# LA200-GZ.net
KiCad netlist of a schematic drawn in Altium Designer
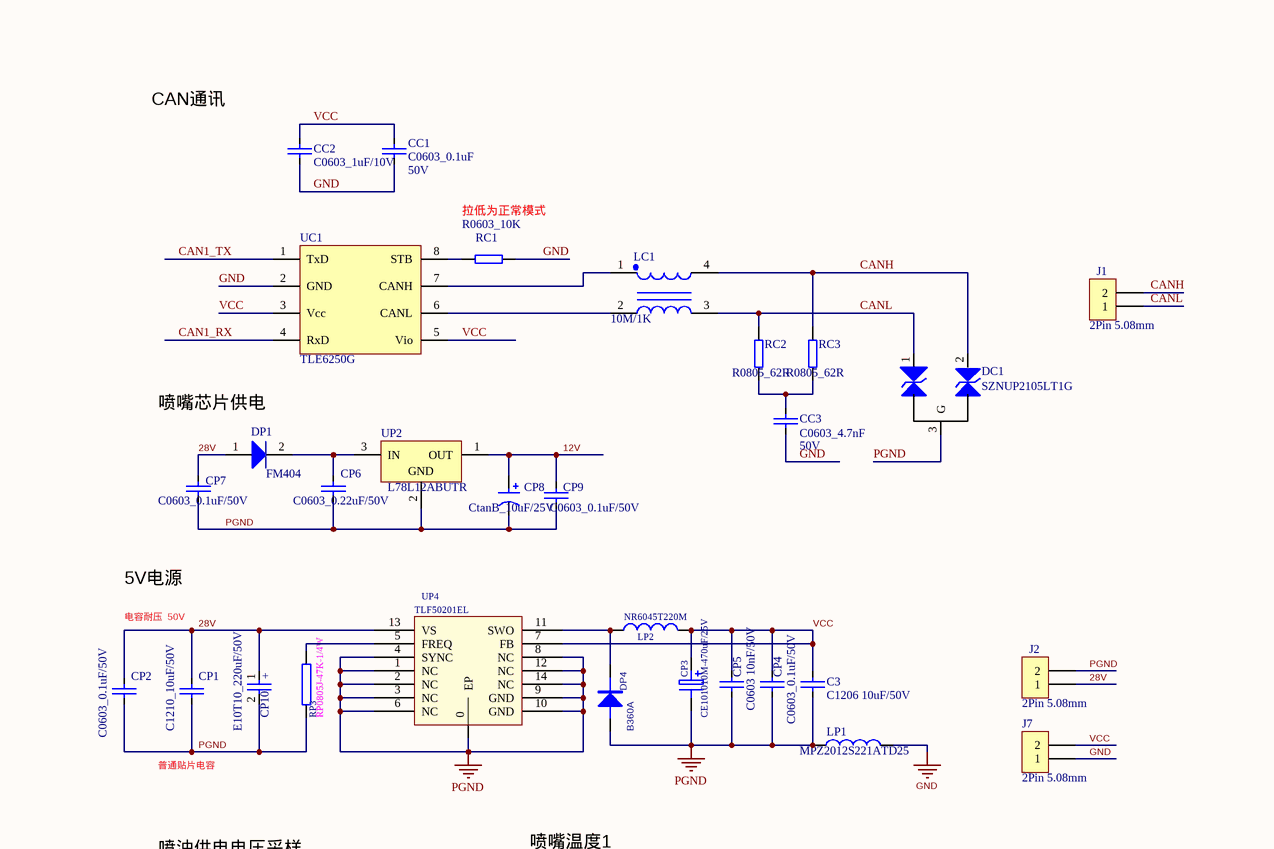
[diagram p0: LA200-GZ.SchDoc, top left]
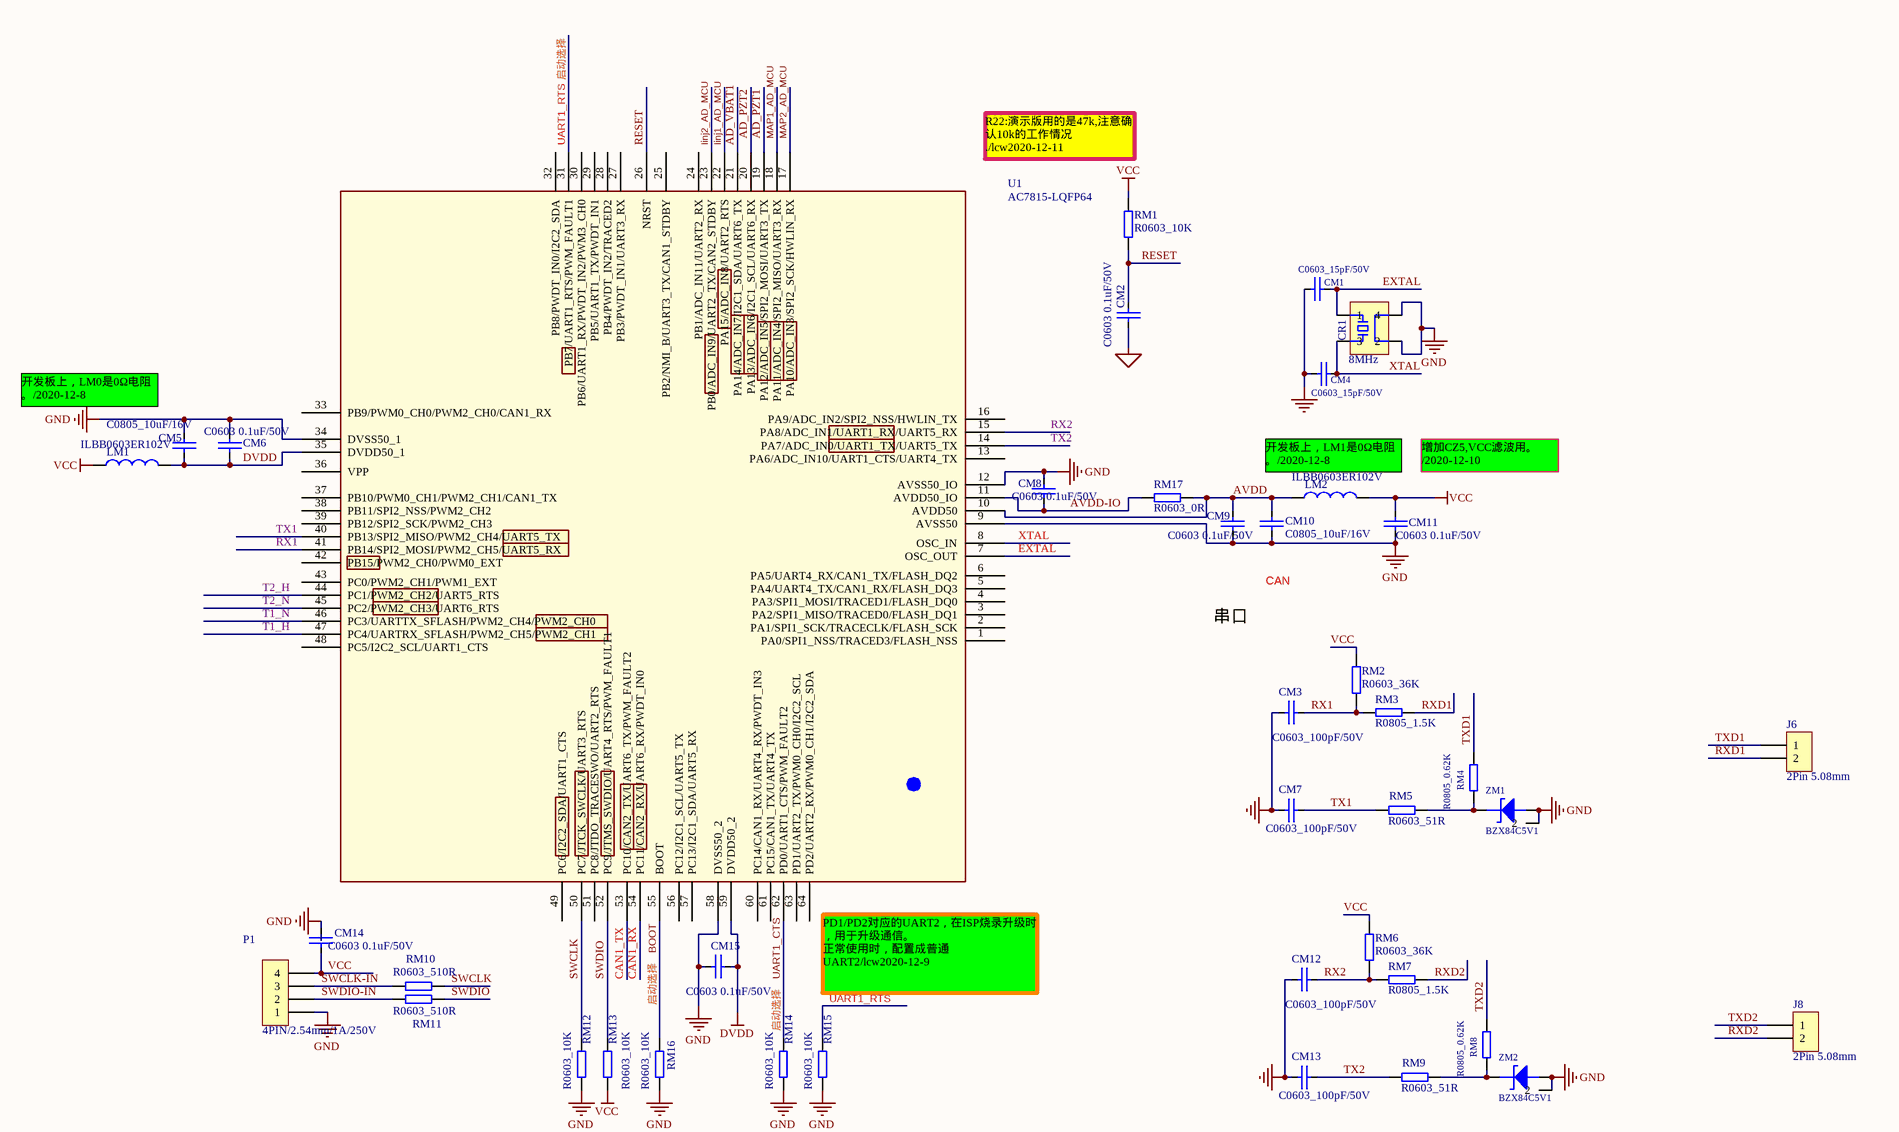
[diagram p1: LA200-GZ.SchDoc, top right]
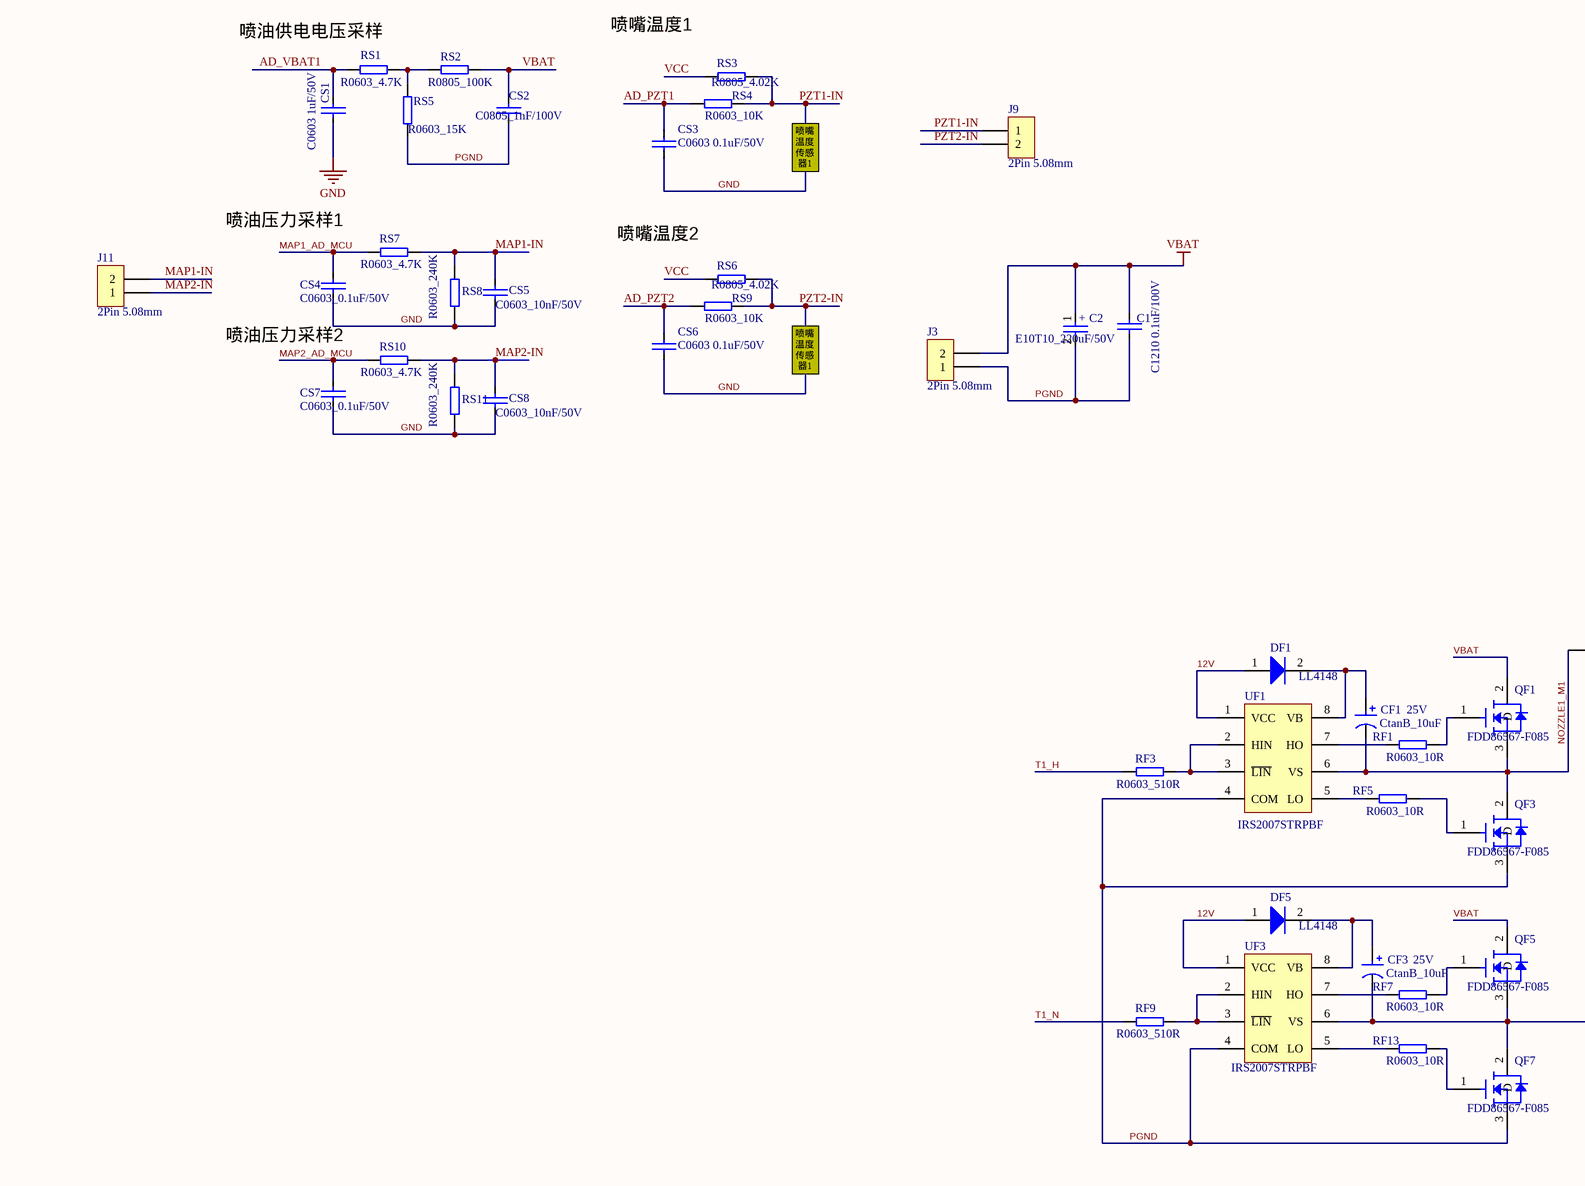
[diagram p2: LA200-GZ.SchDoc, bottom left]
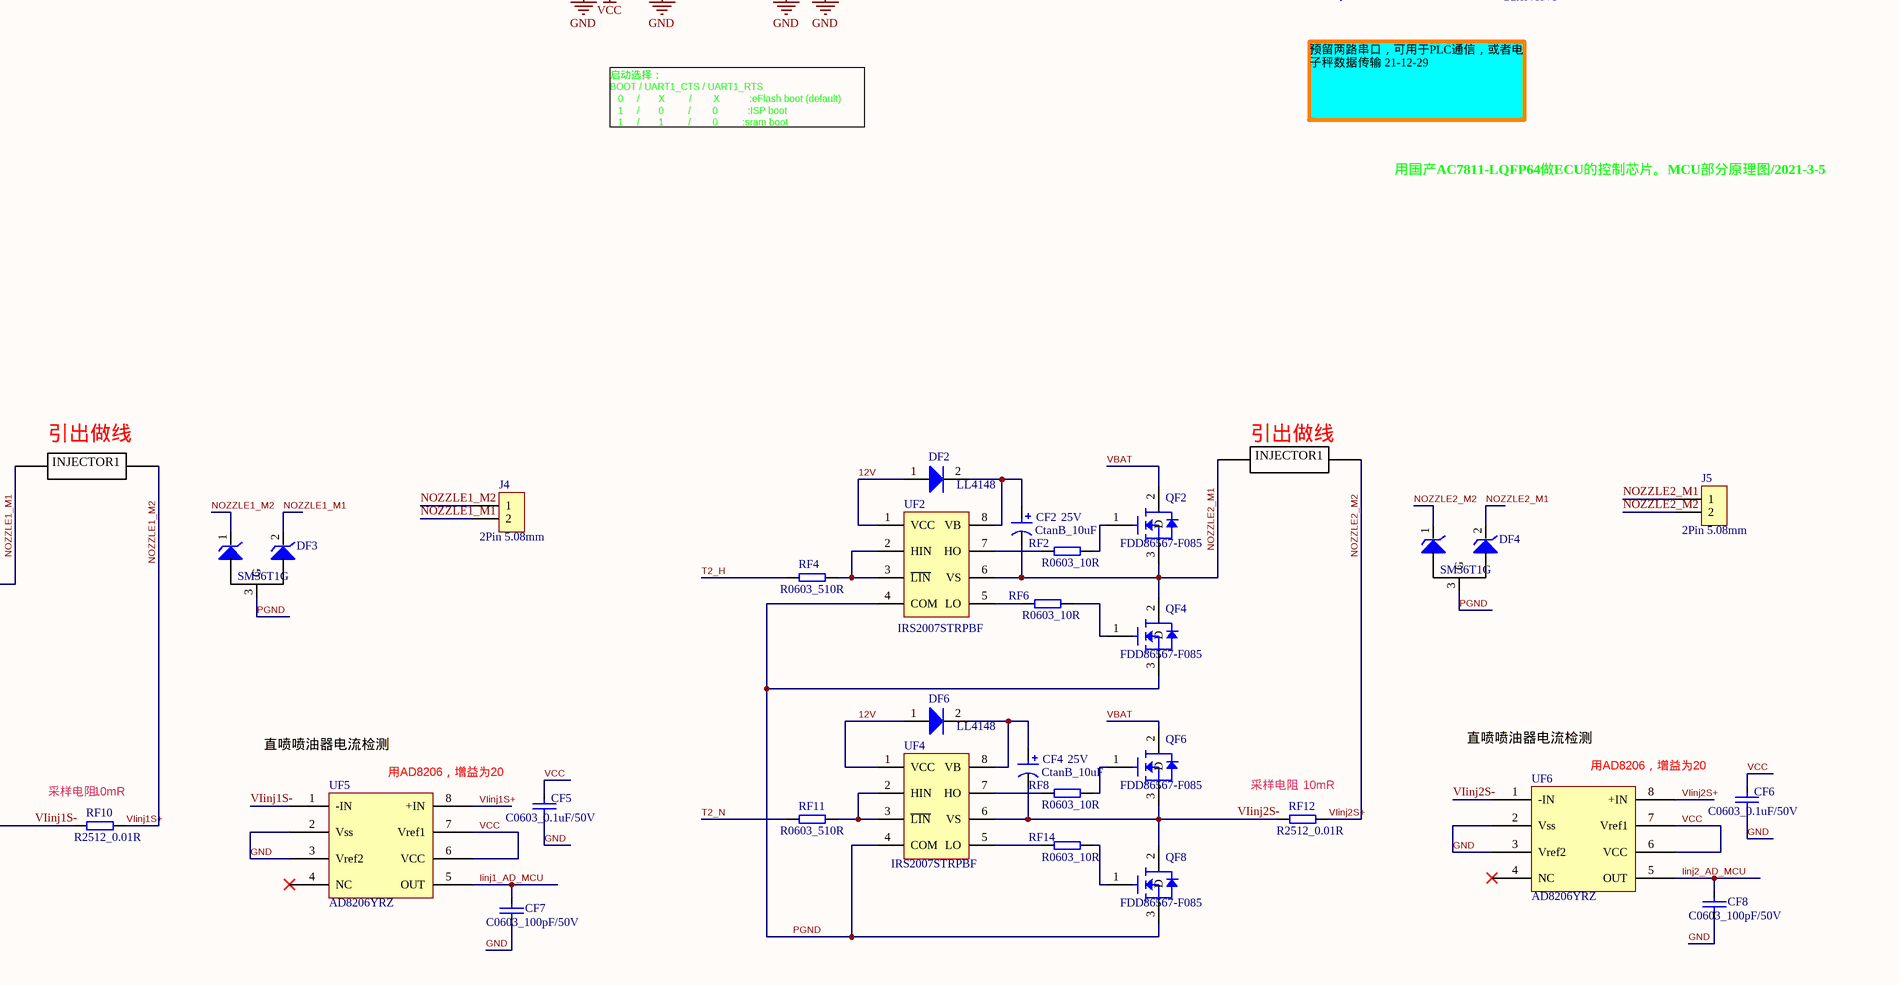
[diagram p3: LA200-GZ.SchDoc, bottom right]

(export (version "E")
  (design (tool "Eeschema 10.0.6"))
  (components
    (comp (ref "C1")
      (value "C1210 0.1uF/100V")
      (footprint "C1210")
      (description "C1210 0.1uF/50V 10%")
      (fields (field (name "VOLTAGE") "100V") (field (name "PART NUMBER") "3170014005"))
      (libsource (lib "BMSer") (part "CAP"))
    )
    (comp (ref "C2")
      (value "E10T10_220uF/50V")
      (footprint "E10T10")
      (description "E10T10 220uF/50V 20%")
      (fields (field (name "PART NUMBER") "3172690040") (field (name "MANUFACTURER") "LELON"))
      (libsource (lib "BMSer") (part "CAP_E"))
    )
    (comp (ref "C3")
      (value "C1206 10uF/50V")
      (footprint "C1206")
      (description "C1206 10uF/50V  10%")
      (fields (field (name "VOLTAGE") "50V") (field (name "PART NUMBER") "3172530019"))
      (libsource (lib "BMSer") (part "CAP"))
    )
    (comp (ref "CC1")
      (value "C0603_0.1uF")
      (footprint "C0603")
      (description "C0603 0.1uF/50V 10%")
      (fields
        (field (name "VOLTAGE") "50V")
        (field (name "PART NUMBER") "3170011015")
        (field (name "MANUFACTURER") "YAGEO")
      )
      (libsource (lib "BMSer") (part "CAP"))
    )
    (comp (ref "CC2")
      (value "C0603_1uF/10V")
      (footprint "C0603")
      (description "C0603 0.1uF/50V 10%")
      (fields (field (name "VOLTAGE") "10V") (field (name "PART NUMBER") "3170011015"))
      (libsource (lib "BMSer") (part "CAP"))
    )
    (comp (ref "CC3")
      (value "C0603_4.7nF")
      (footprint "C0603")
      (description "C0603 4.7nF/50V 5% X7R")
      (fields
        (field (name "VOLTAGE") "50V")
        (field (name "PART NUMBER") "3170011009")
        (field (name "MANUFACTURER") "YAGEO")
      )
      (libsource (lib "BMSer") (part "CAP"))
    )
    (comp (ref "CF1")
      (value "CtanB_10uF")
      (footprint "CTANB")
      (description "CtanB(1210) 10uF/25V 10%")
      (fields
        (field (name "PART NUMBER") "3172690034")
        (field (name "MANUFACTURER") "AVX")
        (field (name "VOLTAGE") "25V")
      )
      (libsource (lib "BMSer") (part "CAP_T"))
    )
    (comp (ref "CF2")
      (value "CtanB_10uF")
      (footprint "CTANB")
      (description "CtanB(1210) 10uF/25V 10%")
      (fields
        (field (name "PART NUMBER") "3172690034")
        (field (name "MANUFACTURER") "AVX")
        (field (name "VOLTAGE") "25V")
      )
      (libsource (lib "BMSer") (part "CAP_T"))
    )
    (comp (ref "CF3")
      (value "CtanB_10uF")
      (footprint "CTANB")
      (description "CtanB(1210) 10uF/25V 10%")
      (fields
        (field (name "PART NUMBER") "3172690034")
        (field (name "MANUFACTURER") "AVX")
        (field (name "VOLTAGE") "25V")
      )
      (libsource (lib "BMSer") (part "CAP_T"))
    )
    (comp (ref "CF4")
      (value "CtanB_10uF")
      (footprint "CTANB")
      (description "CtanB(1210) 10uF/25V 10%")
      (fields
        (field (name "PART NUMBER") "3172690034")
        (field (name "MANUFACTURER") "AVX")
        (field (name "VOLTAGE") "25V")
      )
      (libsource (lib "BMSer") (part "CAP_T"))
    )
    (comp (ref "CF5")
      (value "C0603_0.1uF/50V")
      (footprint "C0603")
      (description "C0603 0.1uF/50V 10%")
      (fields (field (name "VOLTAGE") "50V") (field (name "PART NUMBER") "3170011015"))
      (libsource (lib "BMSer") (part "CAP"))
    )
    (comp (ref "CF6")
      (value "C0603_0.1uF/50V")
      (footprint "C0603")
      (description "C0603 0.1uF/50V 10%")
      (fields (field (name "VOLTAGE") "50V") (field (name "PART NUMBER") "3170011015"))
      (libsource (lib "BMSer") (part "CAP"))
    )
    (comp (ref "CF7")
      (value "C0603_100pF/50V")
      (footprint "C0603")
      (description "C0603 100pF/50V 5%")
      (fields (field (name "VOLTAGE") "50V") (field (name "PART NUMBER") "3170011003"))
      (libsource (lib "BMSer") (part "CAP"))
    )
    (comp (ref "CF8")
      (value "C0603_100pF/50V")
      (footprint "C0603")
      (description "C0603 100pF/50V 5%")
      (fields (field (name "VOLTAGE") "50V") (field (name "PART NUMBER") "3170011003"))
      (libsource (lib "BMSer") (part "CAP"))
    )
    (comp (ref "CM1")
      (value "C0603_15pF/50V")
      (footprint "C0603")
      (description "C0603 15pF/50V 10%")
      (fields (field (name "VOLTAGE") "50V") (field (name "PART NUMBER") "3172510040"))
      (libsource (lib "BMSer") (part "CAP"))
    )
    (comp (ref "CM2")
      (value "C0603 0.1uF/50V")
      (footprint "C0603")
      (description "C0603 0.1uF/50V 10%")
      (fields (field (name "VOLTAGE") "50V") (field (name "PART NUMBER") "3170011015"))
      (libsource (lib "BMSer") (part "CAP"))
    )
    (comp (ref "CM3")
      (value "C0603_100pF/50V")
      (footprint "C0603")
      (description "C0603 100pF/50V 5%")
      (fields (field (name "VOLTAGE") "50V") (field (name "PART NUMBER") "3170011003"))
      (libsource (lib "BMSer") (part "CAP"))
    )
    (comp (ref "CM4")
      (value "C0603_15pF/50V")
      (footprint "C0603")
      (description "C0603 15pF/50V 10%")
      (fields (field (name "VOLTAGE") "50V") (field (name "PART NUMBER") "3172510040"))
      (libsource (lib "BMSer") (part "CAP"))
    )
    (comp (ref "CM5")
      (value "C0805_10uF/16V")
      (footprint "C0805")
      (description "C0805 10uF/16V 10%")
      (fields (field (name "VOLTAGE") "16V") (field (name "PART NUMBER") "3170012008"))
      (libsource (lib "BMSer") (part "CAP"))
    )
    (comp (ref "CM6")
      (value "C0603 0.1uF/50V")
      (footprint "C0603")
      (description "C0603 0.1uF/50V 10%")
      (fields (field (name "VOLTAGE") "50V") (field (name "PART NUMBER") "3170011015"))
      (libsource (lib "BMSer") (part "CAP"))
    )
    (comp (ref "CM7")
      (value "C0603_100pF/50V")
      (footprint "C0603")
      (description "C0603 100pF/50V 5%")
      (fields (field (name "VOLTAGE") "50V") (field (name "PART NUMBER") "3170011003"))
      (libsource (lib "BMSer") (part "CAP"))
    )
    (comp (ref "CM8")
      (value "C0603 0.1uF/50V")
      (footprint "C0603")
      (description "C0603 0.1uF/50V 10%")
      (fields (field (name "VOLTAGE") "50V") (field (name "PART NUMBER") "3170011015"))
      (libsource (lib "BMSer") (part "CAP"))
    )
    (comp (ref "CM9")
      (value "C0603 0.1uF/50V")
      (footprint "C0603")
      (description "C0603 0.1uF/50V 10%")
      (fields (field (name "VOLTAGE") "50V") (field (name "PART NUMBER") "3170011015"))
      (libsource (lib "BMSer") (part "CAP"))
    )
    (comp (ref "CM10")
      (value "C0805_10uF/16V")
      (footprint "C0805")
      (description "C0805 10uF/16V 10%")
      (fields (field (name "VOLTAGE") "16V") (field (name "PART NUMBER") "3170012008"))
      (libsource (lib "BMSer") (part "CAP"))
    )
    (comp (ref "CM11")
      (value "C0603 0.1uF/50V")
      (footprint "C0603")
      (description "C0603 0.1uF/50V 10%")
      (fields (field (name "VOLTAGE") "50V") (field (name "PART NUMBER") "3170011015"))
      (libsource (lib "BMSer") (part "CAP"))
    )
    (comp (ref "CM12")
      (value "C0603_100pF/50V")
      (footprint "C0603")
      (description "C0603 100pF/50V 5%")
      (fields (field (name "VOLTAGE") "50V") (field (name "PART NUMBER") "3170011003"))
      (libsource (lib "BMSer") (part "CAP"))
    )
    (comp (ref "CM13")
      (value "C0603_100pF/50V")
      (footprint "C0603")
      (description "C0603 100pF/50V 5%")
      (fields (field (name "VOLTAGE") "50V") (field (name "PART NUMBER") "3170011003"))
      (libsource (lib "BMSer") (part "CAP"))
    )
    (comp (ref "CM14")
      (value "C0603 0.1uF/50V")
      (footprint "C0603")
      (description "C0603 0.1uF/50V 10%")
      (fields (field (name "VOLTAGE") "50V") (field (name "PART NUMBER") "3170011015"))
      (libsource (lib "BMSer") (part "CAP"))
    )
    (comp (ref "CM15")
      (value "C0603 0.1uF/50V")
      (footprint "C0603")
      (description "C0603 0.1uF/50V 10%")
      (fields (field (name "VOLTAGE") "50V") (field (name "PART NUMBER") "3170011015"))
      (libsource (lib "BMSer") (part "CAP"))
    )
    (comp (ref "CP1")
      (value "C1210_10uF/50V")
      (footprint "C1210")
      (description "C1210 10uF/50V 10%")
      (fields (field (name "VOLTAGE") "50V") (field (name "PART NUMBER") "3170014011"))
      (libsource (lib "BMSer") (part "CAP"))
    )
    (comp (ref "CP2")
      (value "C0603_0.1uF/50V")
      (footprint "C0603")
      (description "C0603 0.1uF/50V 10%")
      (fields (field (name "VOLTAGE") "50V") (field (name "PART NUMBER") "3170011015"))
      (libsource (lib "BMSer") (part "CAP"))
    )
    (comp (ref "CP3")
      (value "CE101010M-470uF/25V")
      (footprint "E10T10")
      (libsource (lib "*") (part "ELECTRO1"))
    )
    (comp (ref "CP4")
      (value "C0603_0.1uF/50V")
      (footprint "C0603")
      (description "C0603 0.1uF/50V 10%")
      (fields (field (name "VOLTAGE") "50V") (field (name "PART NUMBER") "3170011015"))
      (libsource (lib "BMSer") (part "CAP"))
    )
    (comp (ref "CP5")
      (value "C0603 10nF/50V")
      (footprint "C0603")
      (description "C0603 10nF/50V  10%")
      (fields (field (name "VOLTAGE") "50V") (field (name "PART NUMBER") "3170011011"))
      (libsource (lib "BMSer") (part "CAP"))
    )
    (comp (ref "CP6")
      (value "C0603_0.22uF/50V")
      (footprint "C0603")
      (description "C0603 0.22uF/50V 10%")
      (fields (field (name "VOLTAGE") "50V") (field (name "PART NUMBER") "3172510028"))
      (libsource (lib "BMSer") (part "CAP"))
    )
    (comp (ref "CP7")
      (value "C0603_0.1uF/50V")
      (footprint "C0603")
      (description "C0603 0.1uF/50V 10%")
      (fields (field (name "VOLTAGE") "50V") (field (name "PART NUMBER") "3170011015"))
      (libsource (lib "BMSer") (part "CAP"))
    )
    (comp (ref "CP8")
      (value "CtanB_10uF/25V")
      (footprint "CTANB")
      (description "CtanB(1210) 10uF/25V 10%")
      (fields (field (name "PART NUMBER") "3172690034") (field (name "MANUFACTURER") "AVX"))
      (libsource (lib "BMSer") (part "CAP_T"))
    )
    (comp (ref "CP9")
      (value "C0603_0.1uF/50V")
      (footprint "C0603")
      (description "C0603 0.1uF/50V 10%")
      (fields (field (name "VOLTAGE") "50V") (field (name "PART NUMBER") "3170011015"))
      (libsource (lib "BMSer") (part "CAP"))
    )
    (comp (ref "CP10")
      (value "E10T10_220uF/50V")
      (footprint "E10T10")
      (description "E10T10 220uF/50V 20%")
      (fields (field (name "PART NUMBER") "3172690040") (field (name "MANUFACTURER") "LELON"))
      (libsource (lib "BMSer") (part "CAP_E"))
    )
    (comp (ref "CR1")
      (value "8MHz")
      (footprint "5.0*3.2*0.9mm AB")
      (description "5.0*3.2*0.9mm AB 8MHz")
      (fields (field (name "PART NUMBER") "53120010024") (field (name "MANUFACTURER") "TXC"))
      (libsource (lib "BMSer") (part "XTAL_1"))
    )
    (comp (ref "CS1")
      (value "C0603 1uF/50V")
      (footprint "C0603")
      (description "C0603 1uF/50V 10%")
      (fields (field (name "VOLTAGE") "50V") (field (name "PART NUMBER") "3172510036"))
      (libsource (lib "BMSer") (part "CAP"))
    )
    (comp (ref "CS2")
      (value "C0805_1nF/100V")
      (footprint "C0805")
      (description "C0805 1nF/100V 10%")
      (fields (field (name "VOLTAGE") "100V") (field (name "PART NUMBER") "3172520028"))
      (libsource (lib "BMSer") (part "CAP"))
    )
    (comp (ref "CS3")
      (value "C0603 0.1uF/50V")
      (footprint "C0603")
      (description "C0603 0.1uF/50V 10%")
      (fields (field (name "VOLTAGE") "50V") (field (name "PART NUMBER") "3170011015"))
      (libsource (lib "BMSer") (part "CAP"))
    )
    (comp (ref "CS4")
      (value "C0603_0.1uF/50V")
      (footprint "C0603")
      (description "C0603 0.1uF/50V 10%")
      (fields (field (name "VOLTAGE") "50V") (field (name "PART NUMBER") "3170011015"))
      (libsource (lib "BMSer") (part "CAP"))
    )
    (comp (ref "CS5")
      (value "C0603_10nF/50V")
      (footprint "C0603")
      (description "C0603 10nF/50V  10%")
      (fields (field (name "VOLTAGE") "50V") (field (name "PART NUMBER") "3170011011"))
      (libsource (lib "BMSer") (part "CAP"))
    )
    (comp (ref "CS6")
      (value "C0603 0.1uF/50V")
      (footprint "C0603")
      (description "C0603 0.1uF/50V 10%")
      (fields (field (name "VOLTAGE") "50V") (field (name "PART NUMBER") "3170011015"))
      (libsource (lib "BMSer") (part "CAP"))
    )
    (comp (ref "CS7")
      (value "C0603_0.1uF/50V")
      (footprint "C0603")
      (description "C0603 0.1uF/50V 10%")
      (fields (field (name "VOLTAGE") "50V") (field (name "PART NUMBER") "3170011015"))
      (libsource (lib "BMSer") (part "CAP"))
    )
    (comp (ref "CS8")
      (value "C0603_10nF/50V")
      (footprint "C0603")
      (description "C0603 10nF/50V  10%")
      (fields (field (name "VOLTAGE") "50V") (field (name "PART NUMBER") "3170011011"))
      (libsource (lib "BMSer") (part "CAP"))
    )
    (comp (ref "DC1")
      (value "SZNUP2105LT1G")
      (footprint "SOT-23")
      (description "SOT-23 SZNUP2105LT1G")
      (fields (field (name "PART NUMBER") "3110050073") (field (name "MANUFACTURER") "ON"))
      (libsource (lib "BMSer") (part "SZNUP2105LT1G"))
    )
    (comp (ref "DF1")
      (value "LL4148")
      (footprint "SOD-80")
      (description "SOD-80  LL4148 2A/75V")
      (fields (field (name "PART NUMBER") "3110010015") (field (name "MANUFACTURER") "VISHA"))
      (libsource (lib "BMSer") (part "DIODE"))
    )
    (comp (ref "DF2")
      (value "LL4148")
      (footprint "SOD-80")
      (description "SOD-80  LL4148 2A/75V")
      (fields (field (name "PART NUMBER") "3110010015") (field (name "MANUFACTURER") "VISHA"))
      (libsource (lib "BMSer") (part "DIODE"))
    )
    (comp (ref "DF3")
      (value "SM36T1G")
      (footprint "SOT-23")
      (description "SOT-23 SM36T1G")
      (fields (field (name "PART NUMBER") "3110050074") (field (name "MANUFACTURER") "ON"))
      (libsource (lib "BMSer") (part "SM36T1G"))
    )
    (comp (ref "DF4")
      (value "SM36T1G")
      (footprint "SOT-23")
      (description "SOT-23 SM36T1G")
      (fields (field (name "PART NUMBER") "3110050074") (field (name "MANUFACTURER") "ON"))
      (libsource (lib "BMSer") (part "SM36T1G"))
    )
    (comp (ref "DF5")
      (value "LL4148")
      (footprint "SOD-80")
      (description "SOD-80  LL4148 2A/75V")
      (fields (field (name "PART NUMBER") "3110010015") (field (name "MANUFACTURER") "VISHA"))
      (libsource (lib "BMSer") (part "DIODE"))
    )
    (comp (ref "DF6")
      (value "LL4148")
      (footprint "SOD-80")
      (description "SOD-80  LL4148 2A/75V")
      (fields (field (name "PART NUMBER") "3110010015") (field (name "MANUFACTURER") "VISHA"))
      (libsource (lib "BMSer") (part "DIODE"))
    )
    (comp (ref "DP1")
      (value "FM404")
      (footprint "D0-214AC")
      (description "D0-214AC FM404")
      (fields (field (name "PART NUMBER") "13110010013") (field (name "MANUFACTURER") "LRC"))
      (libsource (lib "BMSer") (part "DIODE"))
    )
    (comp (ref "DP4")
      (value "B360A")
      (footprint "SMA-DIODE")
      (description "60V,1A,肖特基二极管")
      (libsource (lib "*") (part "DIODE"))
    )
    (comp (ref "J1")
      (value "2Pin 5.08mm")
      (footprint "CONN-TH_2P-P5.08_DB128L-5.08-2P")
      (description "691311500002 2Pin 5.08mm 公头")
      (fields (field (name "PART NUMBER") "31900010141") (field (name "MANUFACTURER") "WE"))
      (libsource (lib "") (part "CON2_1"))
    )
    (comp (ref "J2")
      (value "2Pin 5.08mm")
      (footprint "CONN-TH_2P-P5.08_DB128L-5.08-2P")
      (description "691311500002 2Pin 5.08mm 公头")
      (fields (field (name "PART NUMBER") "31900010141") (field (name "MANUFACTURER") "WE"))
      (libsource (lib "") (part "CON2_1"))
    )
    (comp (ref "J3")
      (value "2Pin 5.08mm")
      (footprint "CONN-TH_2P-P5.08_DB128L-5.08-2P")
      (description "691311500002 2Pin 5.08mm 公头")
      (fields (field (name "PART NUMBER") "31900010141") (field (name "MANUFACTURER") "WE"))
      (libsource (lib "") (part "CON2_1"))
    )
    (comp (ref "J4")
      (value "2Pin 5.08mm")
      (footprint "CONN-TH_2P-P5.08_DB128L-5.08-2P")
      (description "691311500002 2Pin 5.08mm 公头")
      (fields (field (name "PART NUMBER") "31900010141") (field (name "MANUFACTURER") "WE"))
      (libsource (lib "BMSer") (part "CON2"))
    )
    (comp (ref "J5")
      (value "2Pin 5.08mm")
      (footprint "CONN-TH_2P-P5.08_DB128L-5.08-2P")
      (description "691311500002 2Pin 5.08mm 公头")
      (fields (field (name "PART NUMBER") "31900010141") (field (name "MANUFACTURER") "WE"))
      (libsource (lib "BMSer") (part "CON2"))
    )
    (comp (ref "J6")
      (value "2Pin 5.08mm")
      (footprint "CONN-TH_2P-P5.08_DB128L-5.08-2P")
      (description "691311500002 2Pin 5.08mm 公头")
      (fields (field (name "PART NUMBER") "31900010141") (field (name "MANUFACTURER") "WE"))
      (libsource (lib "BMSer") (part "CON2"))
    )
    (comp (ref "J7")
      (value "2Pin 5.08mm")
      (footprint "CONN-TH_2P-P5.08_DB128L-5.08-2P")
      (description "691311500002 2Pin 5.08mm 公头")
      (fields (field (name "PART NUMBER") "31900010141") (field (name "MANUFACTURER") "WE"))
      (libsource (lib "") (part "CON2_1"))
    )
    (comp (ref "J8")
      (value "2Pin 5.08mm")
      (footprint "CONN-TH_2P-P5.08_DB128L-5.08-2P")
      (description "691311500002 2Pin 5.08mm 公头")
      (fields (field (name "PART NUMBER") "31900010141") (field (name "MANUFACTURER") "WE"))
      (libsource (lib "BMSer") (part "CON2"))
    )
    (comp (ref "J9")
      (value "2Pin 5.08mm")
      (footprint "CONN-TH_2P-P5.08_DB128L-5.08-2P")
      (description "691311500002 2Pin 5.08mm 公头")
      (fields (field (name "PART NUMBER") "31900010141") (field (name "MANUFACTURER") "WE"))
      (libsource (lib "BMSer") (part "CON2"))
    )
    (comp (ref "J11")
      (value "2Pin 5.08mm")
      (footprint "CONN-TH_2P-P5.08_DB128L-5.08-2P")
      (description "691311500002 2Pin 5.08mm 公头")
      (fields (field (name "PART NUMBER") "31900010141") (field (name "MANUFACTURER") "WE"))
      (libsource (lib "") (part "CON2_1"))
    )
    (comp (ref "LC1")
      (value "10M/1K")
      (footprint "ACT45B")
      (description "ACT45B-510-2P-TL  10M/1K/0.2A")
      (fields (field (name "PART NUMBER") "3180020022") (field (name "MANUFACTURER") "TDK"))
      (libsource (lib "BMSer") (part "INDUCTOR3"))
    )
    (comp (ref "LM1")
      (value "ILBB0603ER102V")
      (footprint "L0603")
      (description "L0603 ILBB0603ER102V")
      (fields (field (name "PART NUMBER") "3180020002") (field (name "MANUFACTURER") "Vishay"))
      (libsource (lib "BMSer") (part "INDUCTOR1"))
    )
    (comp (ref "LM2")
      (value "ILBB0603ER102V")
      (footprint "L0603")
      (description "L0603 ILBB0603ER102V")
      (fields (field (name "PART NUMBER") "3180020002") (field (name "MANUFACTURER") "Vishay"))
      (libsource (lib "BMSer") (part "INDUCTOR1"))
    )
    (comp (ref "LP1")
      (value "MPZ2012S221ATD25")
      (footprint "L 0805")
      (description "L0805 MPZ2012S221ATD25")
      (fields (field (name "PART NUMBER") "53180020011") (field (name "MANUFACTURER") "TDK"))
      (libsource (lib "BMSer") (part "INDUCTOR1"))
    )
    (comp (ref "LP2")
      (value "NR6045T220M")
      (footprint "L_6045")
      (description "22uH/1.9A")
      (libsource (lib "Miscellaneous Devices") (part "Inductor"))
    )
    (comp (ref "P1")
      (value "4PIN/2.54mm/1A/250V")
      (footprint "IDC-SIP-4P-2.54")
      (description "直针插座 CWF25404D180 4PIN/2.54mm/1A/250V")
      (fields (field (name "PART NUMBER") "3190010008") (field (name "MANUFACTURER") "CSCONN 德科泰"))
      (libsource (lib "BMSer") (part "CON4"))
    )
    (comp (ref "QF1")
      (value "FDD86567-F085")
      (footprint "TO-252-3")
      (description "TO-252-3 FDD86567-F085 60V/100A")
      (fields (field (name "PART NUMBER") "53110022012") (field (name "MANUFACTURER") "ON"))
      (libsource (lib "BMSer") (part "NMOSGDS"))
    )
    (comp (ref "QF2")
      (value "FDD86567-F085")
      (footprint "TO-252-3")
      (description "TO-252-3 FDD86567-F085 60V/100A")
      (fields (field (name "PART NUMBER") "53110022012") (field (name "MANUFACTURER") "ON"))
      (libsource (lib "BMSer") (part "NMOSGDS"))
    )
    (comp (ref "QF3")
      (value "FDD86567-F085")
      (footprint "TO-252-3")
      (description "TO-252-3 FDD86567-F085 60V/100A")
      (fields (field (name "PART NUMBER") "53110022012") (field (name "MANUFACTURER") "ON"))
      (libsource (lib "BMSer") (part "NMOSGDS"))
    )
    (comp (ref "QF4")
      (value "FDD86567-F085")
      (footprint "TO-252-3")
      (description "TO-252-3 FDD86567-F085 60V/100A")
      (fields (field (name "PART NUMBER") "53110022012") (field (name "MANUFACTURER") "ON"))
      (libsource (lib "BMSer") (part "NMOSGDS"))
    )
    (comp (ref "QF5")
      (value "FDD86567-F085")
      (footprint "TO-252-3")
      (description "TO-252-3 FDD86567-F085 60V/100A")
      (fields (field (name "PART NUMBER") "53110022012") (field (name "MANUFACTURER") "ON"))
      (libsource (lib "BMSer") (part "NMOSGDS"))
    )
    (comp (ref "QF6")
      (value "FDD86567-F085")
      (footprint "TO-252-3")
      (description "TO-252-3 FDD86567-F085 60V/100A")
      (fields (field (name "PART NUMBER") "53110022012") (field (name "MANUFACTURER") "ON"))
      (libsource (lib "BMSer") (part "NMOSGDS"))
    )
    (comp (ref "QF7")
      (value "FDD86567-F085")
      (footprint "TO-252-3")
      (description "TO-252-3 FDD86567-F085 60V/100A")
      (fields (field (name "PART NUMBER") "53110022012") (field (name "MANUFACTURER") "ON"))
      (libsource (lib "BMSer") (part "NMOSGDS"))
    )
    (comp (ref "QF8")
      (value "FDD86567-F085")
      (footprint "TO-252-3")
      (description "TO-252-3 FDD86567-F085 60V/100A")
      (fields (field (name "PART NUMBER") "53110022012") (field (name "MANUFACTURER") "ON"))
      (libsource (lib "BMSer") (part "NMOSGDS"))
    )
    (comp (ref "RC1")
      (value "R0603_10K")
      (footprint "R0603")
      (description "R0603 1/10w 10K 1%")
      (fields (field (name "PART NUMBER") "3160030053") (field (name "MANUFACTURER") "YAGEO"))
      (libsource (lib "BMSer") (part "RS"))
    )
    (comp (ref "RC2")
      (value "R0805_62R")
      (footprint "R0805")
      (description "R0805 1/8w10R 1%")
      (fields (field (name "PART NUMBER") "3160050016") (field (name "MANUFACTURER") "YAGEO"))
      (libsource (lib "BMSer") (part "RS"))
    )
    (comp (ref "RC3")
      (value "R0805_62R")
      (footprint "R0805")
      (description "R0805 1/8w10R 1%")
      (fields (field (name "PART NUMBER") "3160050016") (field (name "MANUFACTURER") "YAGEO"))
      (libsource (lib "BMSer") (part "RS"))
    )
    (comp (ref "RF1")
      (value "R0603_10R")
      (footprint "R0603")
      (description "R0603 1/10w  10R 1%")
      (fields (field (name "PART NUMBER") "3160030193") (field (name "MANUFACTURER") "YAGEO"))
      (libsource (lib "BMSer") (part "RS"))
    )
    (comp (ref "RF2")
      (value "R0603_10R")
      (footprint "R0603")
      (description "R0603 1/10w  10R 1%")
      (fields (field (name "PART NUMBER") "3160030193") (field (name "MANUFACTURER") "YAGEO"))
      (libsource (lib "BMSer") (part "RS"))
    )
    (comp (ref "RF3")
      (value "R0603_510R")
      (footprint "R0603")
      (description "R0603  1/10w 510R 1%")
      (fields (field (name "PART NUMBER") "3160030020") (field (name "MANUFACTURER") "YAGEO"))
      (libsource (lib "BMSer") (part "RS"))
    )
    (comp (ref "RF4")
      (value "R0603_510R")
      (footprint "R0603")
      (description "R0603  1/10w 510R 1%")
      (fields (field (name "PART NUMBER") "3160030020") (field (name "MANUFACTURER") "YAGEO"))
      (libsource (lib "BMSer") (part "RS"))
    )
    (comp (ref "RF5")
      (value "R0603_10R")
      (footprint "R0603")
      (description "R0603 1/10w  10R 1%")
      (fields (field (name "PART NUMBER") "3160030193") (field (name "MANUFACTURER") "YAGEO"))
      (libsource (lib "BMSer") (part "RS"))
    )
    (comp (ref "RF6")
      (value "R0603_10R")
      (footprint "R0603")
      (description "R0603 1/10w  10R 1%")
      (fields (field (name "PART NUMBER") "3160030193") (field (name "MANUFACTURER") "YAGEO"))
      (libsource (lib "BMSer") (part "RS"))
    )
    (comp (ref "RF7")
      (value "R0603_10R")
      (footprint "R0603")
      (description "R0603 1/10w  10R 1%")
      (fields (field (name "PART NUMBER") "3160030193") (field (name "MANUFACTURER") "YAGEO"))
      (libsource (lib "BMSer") (part "RS"))
    )
    (comp (ref "RF8")
      (value "R0603_10R")
      (footprint "R0603")
      (description "R0603 1/10w  10R 1%")
      (fields (field (name "PART NUMBER") "3160030193") (field (name "MANUFACTURER") "YAGEO"))
      (libsource (lib "BMSer") (part "RS"))
    )
    (comp (ref "RF9")
      (value "R0603_510R")
      (footprint "R0603")
      (description "R0603  1/10w 510R 1%")
      (fields (field (name "PART NUMBER") "3160030020") (field (name "MANUFACTURER") "YAGEO"))
      (libsource (lib "BMSer") (part "RS"))
    )
    (comp (ref "RF10")
      (value "R2512_0.01R")
      (footprint "R2512")
      (description "R2512 1W 0.01R 1%")
      (fields (field (name "PART NUMBER") "3162380033") (field (name "MANUFACTURER") "YAGEO"))
      (libsource (lib "BMSer") (part "RS"))
    )
    (comp (ref "RF11")
      (value "R0603_510R")
      (footprint "R0603")
      (description "R0603  1/10w 510R 1%")
      (fields (field (name "PART NUMBER") "3160030020") (field (name "MANUFACTURER") "YAGEO"))
      (libsource (lib "BMSer") (part "RS"))
    )
    (comp (ref "RF12")
      (value "R2512_0.01R")
      (footprint "R2512")
      (description "R2512 1W 0.01R 1%")
      (fields (field (name "PART NUMBER") "3162380033") (field (name "MANUFACTURER") "YAGEO"))
      (libsource (lib "BMSer") (part "RS"))
    )
    (comp (ref "RF13")
      (value "R0603_10R")
      (footprint "R0603")
      (description "R0603 1/10w  10R 1%")
      (fields (field (name "PART NUMBER") "3160030193") (field (name "MANUFACTURER") "YAGEO"))
      (libsource (lib "BMSer") (part "RS"))
    )
    (comp (ref "RF14")
      (value "R0603_10R")
      (footprint "R0603")
      (description "R0603 1/10w  10R 1%")
      (fields (field (name "PART NUMBER") "3160030193") (field (name "MANUFACTURER") "YAGEO"))
      (libsource (lib "BMSer") (part "RS"))
    )
    (comp (ref "RM1")
      (value "R0603_10K")
      (footprint "R0603")
      (description "R0603 1/10w 10K")
      (fields (field (name "PART NUMBER") "3160030053") (field (name "MANUFACTURER") "YAGEO"))
      (libsource (lib "BMSer") (part "RS"))
    )
    (comp (ref "RM2")
      (value "R0603_36K")
      (footprint "R0603")
      (description "R0603 1/10w  36K 1%")
      (fields (field (name "PART NUMBER") "3160030087") (field (name "MANUFACTURER") "YAGEO"))
      (libsource (lib "BMSer") (part "RS"))
    )
    (comp (ref "RM3")
      (value "R0805_1.5K")
      (footprint "R0805")
      (description "R0805 1/8w 1.5K 1%最好用1/4w")
      (fields (field (name "PART NUMBER") "13162320038") (field (name "MANUFACTURER") "YAGEO"))
      (libsource (lib "BMSer") (part "RS"))
    )
    (comp (ref "RM4")
      (value "R0805_0.62K")
      (footprint "R0805")
      (description "R0805 1/8w 0.62K 1% 需要1/4w")
      (fields (field (name "PART NUMBER") "3162320027") (field (name "MANUFACTURER") "YAGEO"))
      (libsource (lib "BMSer") (part "RS"))
    )
    (comp (ref "RM5")
      (value "R0603_51R")
      (footprint "R0603")
      (description "R0603  1/10w 51R 1%或100欧")
      (fields (field (name "PART NUMBER") "3160030013") (field (name "MANUFACTURER") "YAGEO"))
      (libsource (lib "BMSer") (part "RS"))
    )
    (comp (ref "RM6")
      (value "R0603_36K")
      (footprint "R0603")
      (description "R0603 1/10w  36K 1%")
      (fields (field (name "PART NUMBER") "3160030087") (field (name "MANUFACTURER") "YAGEO"))
      (libsource (lib "BMSer") (part "RS"))
    )
    (comp (ref "RM7")
      (value "R0805_1.5K")
      (footprint "R0805")
      (description "R0805 1/8w 1.5K 1%最好用1/4w")
      (fields (field (name "PART NUMBER") "13162320038") (field (name "MANUFACTURER") "YAGEO"))
      (libsource (lib "BMSer") (part "RS"))
    )
    (comp (ref "RM8")
      (value "R0805_0.62K")
      (footprint "R0805")
      (description "R0805 1/8w 0.62K 1% 需要1/4w")
      (fields (field (name "PART NUMBER") "3162320027") (field (name "MANUFACTURER") "YAGEO"))
      (libsource (lib "BMSer") (part "RS"))
    )
    (comp (ref "RM9")
      (value "R0603_51R")
      (footprint "R0603")
      (description "R0603  1/10w 51R 1%或100欧")
      (fields (field (name "PART NUMBER") "3160030013") (field (name "MANUFACTURER") "YAGEO"))
      (libsource (lib "BMSer") (part "RS"))
    )
    (comp (ref "RM10")
      (value "R0603_510R")
      (footprint "R0603")
      (description "R0603  1/10w 510R 1%")
      (fields (field (name "PART NUMBER") "3160030020") (field (name "MANUFACTURER") "YAGEO"))
      (libsource (lib "BMSer") (part "RS"))
    )
    (comp (ref "RM11")
      (value "R0603_510R")
      (footprint "R0603")
      (description "R0603  1/10w 510R 1%")
      (fields (field (name "PART NUMBER") "3160030020") (field (name "MANUFACTURER") "YAGEO"))
      (libsource (lib "BMSer") (part "RS"))
    )
    (comp (ref "RM12")
      (value "R0603_10K")
      (footprint "R0603")
      (description "R0603 1/10w 10K 1%")
      (fields (field (name "PART NUMBER") "3160030053") (field (name "MANUFACTURER") "YAGEO"))
      (libsource (lib "BMSer") (part "RS"))
    )
    (comp (ref "RM13")
      (value "R0603_10K")
      (footprint "R0603")
      (description "R0603 1/10w 10K 1%")
      (fields (field (name "PART NUMBER") "3160030053") (field (name "MANUFACTURER") "YAGEO"))
      (libsource (lib "BMSer") (part "RS"))
    )
    (comp (ref "RM14")
      (value "R0603_10K")
      (footprint "R0603")
      (description "R0603 1/10w 10K 1%")
      (fields (field (name "PART NUMBER") "3160030053") (field (name "MANUFACTURER") "YAGEO"))
      (libsource (lib "BMSer") (part "RS"))
    )
    (comp (ref "RM15")
      (value "R0603_10K")
      (footprint "R0603")
      (description "R0603 1/10w 10K 1%")
      (fields (field (name "PART NUMBER") "3160030053") (field (name "MANUFACTURER") "YAGEO"))
      (libsource (lib "BMSer") (part "RS"))
    )
    (comp (ref "RM16")
      (value "R0603_10K")
      (footprint "R0603")
      (description "R0603 1/10w 10K 1%")
      (fields (field (name "PART NUMBER") "3160030053") (field (name "MANUFACTURER") "YAGEO"))
      (libsource (lib "BMSer") (part "RS"))
    )
    (comp (ref "RM17")
      (value "R0603_0R")
      (footprint "R0603")
      (description "R0603 1/10w 0R 1%")
      (fields (field (name "PART NUMBER") "3160030001") (field (name "MANUFACTURER") "YAGEO/UNIOHM"))
      (libsource (lib "BMSer") (part "RS"))
    )
    (comp (ref "RP3")
      (value "RP0805J-47K-1/4W")
      (footprint "0805_R")
      (description "汽车级电阻，47kΩ")
      (libsource (lib "*") (part "RES2"))
    )
    (comp (ref "RS1")
      (value "R0603_4.7K")
      (footprint "R0603")
      (description "R0603 1/10w  4.7K 1%")
      (fields (field (name "PART NUMBER") "3160030224") (field (name "MANUFACTURER") "YAGEO"))
      (libsource (lib "BMSer") (part "RS"))
    )
    (comp (ref "RS2")
      (value "R0805_100K")
      (footprint "R0805")
      (description "R0805 1/8w 100K 1%")
      (fields (field (name "PART NUMBER") "3160050008") (field (name "MANUFACTURER") "YAGEO"))
      (libsource (lib "BMSer") (part "RS"))
    )
    (comp (ref "RS3")
      (value "R0805_4.02K")
      (footprint "R0805")
      (description "R0805 1/8w 4.02K 1%")
      (fields (field (name "PART NUMBER") "13162320037") (field (name "MANUFACTURER") "YAGEO"))
      (libsource (lib "BMSer") (part "RS"))
    )
    (comp (ref "RS4")
      (value "R0603_10K")
      (footprint "R0603")
      (description "R0603 1/10w 10K")
      (fields (field (name "PART NUMBER") "3160030053") (field (name "MANUFACTURER") "YAGEO"))
      (libsource (lib "BMSer") (part "RS"))
    )
    (comp (ref "RS5")
      (value "R0603_15K")
      (footprint "R0603")
      (description "R0603 1/10w 15K 1%")
      (fields (field (name "PART NUMBER") "3160030062") (field (name "MANUFACTURER") "YAGEO"))
      (libsource (lib "BMSer") (part "RS"))
    )
    (comp (ref "RS6")
      (value "R0805_4.02K")
      (footprint "R0805")
      (description "R0805 1/8w 4.02K 1%")
      (fields (field (name "PART NUMBER") "13162320037") (field (name "MANUFACTURER") "YAGEO"))
      (libsource (lib "BMSer") (part "RS"))
    )
    (comp (ref "RS7")
      (value "R0603_4.7K")
      (footprint "R0603")
      (description "R0603 1/10w  4.7K 1%")
      (fields (field (name "PART NUMBER") "3160030224") (field (name "MANUFACTURER") "YAGEO"))
      (libsource (lib "BMSer") (part "RS"))
    )
    (comp (ref "RS8")
      (value "R0603_240K")
      (footprint "R0603")
      (description "R0603 1/10w 240K 1%")
      (fields (field (name "PART NUMBER") "3160030151") (field (name "MANUFACTURER") "YAGEO"))
      (libsource (lib "BMSer") (part "RS"))
    )
    (comp (ref "RS9")
      (value "R0603_10K")
      (footprint "R0603")
      (description "R0603 1/10w 10K")
      (fields (field (name "PART NUMBER") "3160030053") (field (name "MANUFACTURER") "YAGEO"))
      (libsource (lib "BMSer") (part "RS"))
    )
    (comp (ref "RS10")
      (value "R0603_4.7K")
      (footprint "R0603")
      (description "R0603 1/10w  4.7K 1%")
      (fields (field (name "PART NUMBER") "3160030224") (field (name "MANUFACTURER") "YAGEO"))
      (libsource (lib "BMSer") (part "RS"))
    )
    (comp (ref "RS11")
      (value "R0603_240K")
      (footprint "R0603")
      (description "R0603 1/10w 240K 1%")
      (fields (field (name "PART NUMBER") "3160030151") (field (name "MANUFACTURER") "YAGEO"))
      (libsource (lib "BMSer") (part "RS"))
    )
    (comp (ref "U1")
      (value "AC7815-LQFP64")
      (footprint "LQFP-64_L10.0-W10.0-P0.50-LS12.0-BL-EP5.3")
      (libsource (lib "AC781x_SCH_Symbol") (part "AC7811-LQFP64"))
    )
    (comp (ref "UC1")
      (value "TLE6250G")
      (footprint "PG-DSO-8")
      (description "PG-DSO-8 TLE9251VSJ")
      (fields (field (name "PART NUMBER") "3100050124") (field (name "MANUFACTURER") "infineon"))
      (libsource (lib "BMSer") (part "TLE9251VSJ"))
    )
    (comp (ref "UF1")
      (value "IRS2007STRPBF")
      (footprint "SOIC-8L")
      (description "SOIC-8L IRS2007STRPBF")
      (fields (field (name "PART NUMBER") "3100050121") (field (name "MANUFACTURER") "infineon"))
      (libsource (lib "BMSer") (part "IRS2007STRPBF"))
    )
    (comp (ref "UF2")
      (value "IRS2007STRPBF")
      (footprint "SOIC-8L")
      (description "SOIC-8L IRS2007STRPBF")
      (fields (field (name "PART NUMBER") "3100050121") (field (name "MANUFACTURER") "infineon"))
      (libsource (lib "BMSer") (part "IRS2007STRPBF"))
    )
    (comp (ref "UF3")
      (value "IRS2007STRPBF")
      (footprint "SOIC-8L")
      (description "SOIC-8L IRS2007STRPBF")
      (fields (field (name "PART NUMBER") "3100050121") (field (name "MANUFACTURER") "infineon"))
      (libsource (lib "BMSer") (part "IRS2007STRPBF"))
    )
    (comp (ref "UF4")
      (value "IRS2007STRPBF")
      (footprint "SOIC-8L")
      (description "SOIC-8L IRS2007STRPBF")
      (fields (field (name "PART NUMBER") "3100050121") (field (name "MANUFACTURER") "infineon"))
      (libsource (lib "BMSer") (part "IRS2007STRPBF"))
    )
    (comp (ref "UF5")
      (value "AD8206YRZ")
      (footprint "SO-8_NB")
      (description "SO-8_NB AD8206YRZ")
      (fields (field (name "PART NUMBER") "3100100010") (field (name "MANUFACTURER") "ADI"))
      (libsource (lib "BMSer") (part "AD8206YRZ"))
    )
    (comp (ref "UF6")
      (value "AD8206YRZ")
      (footprint "SO-8_NB")
      (description "SO-8_NB AD8206YRZ")
      (fields (field (name "PART NUMBER") "3100100010") (field (name "MANUFACTURER") "ADI"))
      (libsource (lib "BMSer") (part "AD8206YRZ"))
    )
    (comp (ref "UP2")
      (value "L78L12ABUTR")
      (footprint "SOT-89")
      (description "SOT-89 L78L12ABUTR")
      (fields (field (name "PART NUMBER") "3100050105") (field (name "MANUFACTURER") "ST"))
      (libsource (lib "BMSer") (part "L78L12ABUTR"))
    )
    (comp (ref "UP4")
      (value "TLF50201EL")
      (footprint "SSOP14-EP2")
      (libsource (lib "国六") (part "TLF50201EL"))
    )
    (comp (ref "ZM1")
      (value "BZX84C5V1")
      (footprint "SOT-23AK")
      (description "SOT-23 BZX84C5V1")
      (fields (field (name "PART NUMBER") "3110010088") (field (name "MANUFACTURER") "ON"))
      (libsource (lib "BMSer") (part "ZENER_2"))
    )
    (comp (ref "ZM2")
      (value "BZX84C5V1")
      (footprint "SOT-23AK")
      (description "SOT-23 BZX84C5V1")
      (fields (field (name "PART NUMBER") "3110010088") (field (name "MANUFACTURER") "ON"))
      (libsource (lib "BMSer") (part "ZENER_2"))
    )
  )
  (nets
    (net (code "1") (name "/12V") (class "Default")
      (node (ref "CP8") (pin "1") (pinfunction "1_1") (pintype "passive"))
      (node (ref "CP9") (pin "1") (pintype "passive"))
      (node (ref "DF1") (pin "1") (pinfunction "1_1") (pintype "passive"))
      (node (ref "DF2") (pin "1") (pinfunction "1_1") (pintype "passive"))
      (node (ref "DF5") (pin "1") (pinfunction "1_1") (pintype "passive"))
      (node (ref "DF6") (pin "1") (pinfunction "1_1") (pintype "passive"))
      (node (ref "UF1") (pin "1") (pinfunction "VCC_1") (pintype "passive"))
      (node (ref "UF2") (pin "1") (pinfunction "VCC_1") (pintype "passive"))
      (node (ref "UF3") (pin "1") (pinfunction "VCC_1") (pintype "passive"))
      (node (ref "UF4") (pin "1") (pinfunction "VCC_1") (pintype "passive"))
      (node (ref "UP2") (pin "1") (pinfunction "OUT_1") (pintype "passive"))
    )
    (net (code "2") (name "/28V") (class "Default")
      (node (ref "CP1") (pin "1") (pintype "passive"))
      (node (ref "CP10") (pin "1") (pintype "passive"))
      (node (ref "CP2") (pin "1") (pintype "passive"))
      (node (ref "CP7") (pin "1") (pintype "passive"))
      (node (ref "DP1") (pin "1") (pinfunction "1_1") (pintype "passive"))
      (node (ref "J2") (pin "1") (pinfunction "1_1") (pintype "passive"))
      (node (ref "UP4") (pin "13") (pinfunction "VS_13") (pintype "passive"))
    )
    (net (code "3") (name "/AD_PZT1") (class "Default")
      (node (ref "CS3") (pin "1") (pintype "passive"))
      (node (ref "RS4") (pin "1") (pintype "passive"))
      (node (ref "U1") (pin "19") (pinfunction "PA12/ADC_IN5/SPI2_MOSI/UART3_TX_19") (pintype "passive"))
    )
    (net (code "4") (name "/AD_PZT2") (class "Default")
      (node (ref "CS6") (pin "1") (pintype "passive"))
      (node (ref "RS9") (pin "1") (pintype "passive"))
      (node (ref "U1") (pin "20") (pinfunction "PA13/ADC_IN6/I2C1_SCL/UART6_RX_20") (pintype "passive"))
    )
    (net (code "5") (name "/AD_VBAT1") (class "Default")
      (node (ref "CS1") (pin "1") (pintype "passive"))
      (node (ref "RS1") (pin "1") (pintype "passive"))
      (node (ref "U1") (pin "21") (pinfunction "PA14/ADC_IN7/I2C1_SDA/UART6_TX_21") (pintype "passive"))
    )
    (net (code "6") (name "/AVDD") (class "Default")
      (node (ref "CM10") (pin "1") (pintype "passive"))
      (node (ref "CM9") (pin "1") (pintype "passive"))
      (node (ref "LM2") (pin "1") (pintype "passive"))
      (node (ref "RM17") (pin "2") (pintype "passive"))
      (node (ref "U1") (pin "10") (pinfunction "AVDD50_10") (pintype "passive"))
    )
    (net (code "7") (name "/AVDD-IO") (class "Default")
      (node (ref "CM8") (pin "2") (pintype "passive"))
      (node (ref "RM17") (pin "1") (pintype "passive"))
      (node (ref "U1") (pin "11") (pinfunction "AVDD50_IO_11") (pintype "passive"))
    )
    (net (code "8") (name "/BOOT") (class "Default")
      (node (ref "RM16") (pin "2") (pintype "passive"))
      (node (ref "U1") (pin "55") (pinfunction "BOOT_55") (pintype "passive"))
    )
    (net (code "9") (name "/CAN1_RX") (class "Default")
      (node (ref "U1") (pin "54") (pinfunction "PC11/CAN2_RX/UART6_RX/PWDT_IN0_54") (pintype "passive"))
      (node (ref "UC1") (pin "4") (pinfunction "RxD_4") (pintype "passive"))
    )
    (net (code "10") (name "/CAN1_TX") (class "Default")
      (node (ref "U1") (pin "53") (pinfunction "PC10/CAN2_TX/UART6_TX/PWM_FAULT2_53") (pintype "passive"))
      (node (ref "UC1") (pin "1") (pinfunction "TxD_1") (pintype "passive"))
    )
    (net (code "11") (name "/CANH") (class "Default")
      (node (ref "DC1") (pin "2") (pinfunction "2_2") (pintype "passive"))
      (node (ref "J1") (pin "2") (pinfunction "2_2") (pintype "passive"))
      (node (ref "LC1") (pin "4") (pinfunction "4_4") (pintype "passive"))
      (node (ref "RC3") (pin "2") (pintype "passive"))
    )
    (net (code "12") (name "/CANL") (class "Default")
      (node (ref "DC1") (pin "1") (pinfunction "1_1") (pintype "passive"))
      (node (ref "J1") (pin "1") (pinfunction "1_1") (pintype "passive"))
      (node (ref "LC1") (pin "3") (pinfunction "3_3") (pintype "passive"))
      (node (ref "RC2") (pin "2") (pintype "passive"))
    )
    (net (code "13") (name "/EXTAL") (class "Default")
      (node (ref "CM1") (pin "1") (pintype "passive"))
      (node (ref "CR1") (pin "1") (pinfunction "1_1") (pintype "passive"))
      (node (ref "U1") (pin "7") (pinfunction "OSC_OUT_7") (pintype "passive"))
    )
    (net (code "14") (name "/Iinj1_AD_MCU") (class "Default")
      (node (ref "CF7") (pin "1") (pintype "passive"))
      (node (ref "U1") (pin "22") (pinfunction "PA15/ADC_IN8/UART2_RTS_22") (pintype "passive"))
      (node (ref "UF5") (pin "5") (pinfunction "OUT_5") (pintype "passive"))
    )
    (net (code "15") (name "/Iinj2_AD_MCU") (class "Default")
      (node (ref "CF8") (pin "1") (pintype "passive"))
      (node (ref "U1") (pin "23") (pinfunction "PB0/ADC_IN9/UART2_TX/CAN2_STDBY_23") (pintype "passive"))
      (node (ref "UF6") (pin "5") (pinfunction "OUT_5") (pintype "passive"))
    )
    (net (code "16") (name "/MAP1-IN") (class "Default")
      (node (ref "CS5") (pin "1") (pintype "passive"))
      (node (ref "J11") (pin "2") (pinfunction "2_2") (pintype "passive"))
      (node (ref "RS7") (pin "2") (pintype "passive"))
      (node (ref "RS8") (pin "2") (pintype "passive"))
    )
    (net (code "17") (name "/MAP1_AD_MCU") (class "Default")
      (node (ref "CS4") (pin "1") (pintype "passive"))
      (node (ref "RS7") (pin "1") (pintype "passive"))
      (node (ref "U1") (pin "18") (pinfunction "PA11/ADC_IN4/SPI2_MISO/UART3_RX_18") (pintype "passive"))
    )
    (net (code "18") (name "/MAP2-IN") (class "Default")
      (node (ref "CS8") (pin "1") (pintype "passive"))
      (node (ref "J11") (pin "1") (pinfunction "1_1") (pintype "passive"))
      (node (ref "RS10") (pin "2") (pintype "passive"))
      (node (ref "RS11") (pin "2") (pintype "passive"))
    )
    (net (code "19") (name "/MAP2_AD_MCU") (class "Default")
      (node (ref "CS7") (pin "1") (pintype "passive"))
      (node (ref "RS10") (pin "1") (pintype "passive"))
      (node (ref "U1") (pin "17") (pinfunction "PA10/ADC_IN3/SPI2_SCK/HWLIN_RX_17") (pintype "passive"))
    )
    (net (code "20") (name "/NOZZLE1_M1") (class "Default")
      (node (ref "CF1") (pin "2") (pinfunction "2_2") (pintype "passive"))
      (node (ref "DF3") (pin "2") (pinfunction "2_2") (pintype "passive"))
      (node (ref "J4") (pin "2") (pinfunction "2_2") (pintype "passive"))
      (node (ref "QF1") (pin "3") (pinfunction "S_3") (pintype "passive"))
      (node (ref "QF3") (pin "2") (pinfunction "D_2") (pintype "passive"))
      (node (ref "UF1") (pin "6") (pinfunction "VS_6") (pintype "passive"))
    )
    (net (code "21") (name "/NOZZLE1_M2") (class "Default")
      (node (ref "DF3") (pin "1") (pinfunction "1_1") (pintype "passive"))
      (node (ref "J4") (pin "1") (pinfunction "1_1") (pintype "passive"))
      (node (ref "RF10") (pin "2") (pintype "passive"))
      (node (ref "UF5") (pin "8") (pinfunction "+IN_8") (pintype "passive"))
    )
    (net (code "22") (name "/NOZZLE2_M1") (class "Default")
      (node (ref "CF2") (pin "2") (pinfunction "2_2") (pintype "passive"))
      (node (ref "DF4") (pin "2") (pinfunction "2_2") (pintype "passive"))
      (node (ref "J5") (pin "1") (pinfunction "1_1") (pintype "passive"))
      (node (ref "QF2") (pin "3") (pinfunction "S_3") (pintype "passive"))
      (node (ref "QF4") (pin "2") (pinfunction "D_2") (pintype "passive"))
      (node (ref "UF2") (pin "6") (pinfunction "VS_6") (pintype "passive"))
    )
    (net (code "23") (name "/NOZZLE2_M2") (class "Default")
      (node (ref "DF4") (pin "1") (pinfunction "1_1") (pintype "passive"))
      (node (ref "J5") (pin "2") (pinfunction "2_2") (pintype "passive"))
      (node (ref "RF12") (pin "2") (pintype "passive"))
      (node (ref "UF6") (pin "8") (pinfunction "+IN_8") (pintype "passive"))
    )
    (net (code "24") (name "/PZT1-IN") (class "Default")
      (node (ref "J9") (pin "1") (pinfunction "1_1") (pintype "passive"))
      (node (ref "RS3") (pin "2") (pintype "passive"))
      (node (ref "RS4") (pin "2") (pintype "passive"))
    )
    (net (code "25") (name "/PZT2-IN") (class "Default")
      (node (ref "J9") (pin "2") (pinfunction "2_2") (pintype "passive"))
      (node (ref "RS6") (pin "2") (pintype "passive"))
      (node (ref "RS9") (pin "2") (pintype "passive"))
    )
    (net (code "26") (name "/RESET") (class "Default")
      (node (ref "CM2") (pin "2") (pintype "passive"))
      (node (ref "RM1") (pin "1") (pintype "passive"))
      (node (ref "U1") (pin "26") (pinfunction "NRST_26") (pintype "passive"))
    )
    (net (code "27") (name "/RX1") (class "Default")
      (node (ref "CM3") (pin "2") (pintype "passive"))
      (node (ref "RM2") (pin "1") (pintype "passive"))
      (node (ref "RM3") (pin "1") (pintype "passive"))
      (node (ref "U1") (pin "41") (pinfunction "PB14/SPI2_MOSI/PWM2_CH5/UART5_RX_41") (pintype "passive"))
    )
    (net (code "28") (name "/RX2") (class "Default")
      (node (ref "CM12") (pin "2") (pintype "passive"))
      (node (ref "RM6") (pin "1") (pintype "passive"))
      (node (ref "RM7") (pin "1") (pintype "passive"))
      (node (ref "U1") (pin "15") (pinfunction "PA8/ADC_IN1/UART1_RX/UART5_RX_15") (pintype "passive"))
    )
    (net (code "29") (name "/RXD1") (class "Default")
      (node (ref "J6") (pin "2") (pinfunction "2_2") (pintype "passive"))
      (node (ref "RM3") (pin "2") (pintype "passive"))
    )
    (net (code "30") (name "/RXD2") (class "Default")
      (node (ref "J8") (pin "2") (pinfunction "2_2") (pintype "passive"))
      (node (ref "RM7") (pin "2") (pintype "passive"))
    )
    (net (code "31") (name "/SWCLK") (class "Default")
      (node (ref "RM10") (pin "2") (pintype "passive"))
      (node (ref "RM12") (pin "2") (pintype "passive"))
      (node (ref "U1") (pin "50") (pinfunction "PC7/JTCK_SWCLK/UART3_RTS_50") (pintype "passive"))
    )
    (net (code "32") (name "/SWCLK-IN") (class "Default")
      (node (ref "P1") (pin "3") (pinfunction "3_3") (pintype "passive"))
      (node (ref "RM10") (pin "1") (pintype "passive"))
    )
    (net (code "33") (name "/SWDIO") (class "Default")
      (node (ref "RM11") (pin "2") (pintype "passive"))
      (node (ref "RM13") (pin "2") (pintype "passive"))
      (node (ref "U1") (pin "52") (pinfunction "PC9/JTMS_SWDIO/UART4_RTS/PWM_FAULT1_52") (pintype "passive"))
    )
    (net (code "34") (name "/SWDIO-IN") (class "Default")
      (node (ref "P1") (pin "2") (pinfunction "2_2") (pintype "passive"))
      (node (ref "RM11") (pin "1") (pintype "passive"))
    )
    (net (code "35") (name "/T1_H") (class "Default")
      (node (ref "RF3") (pin "1") (pintype "passive"))
      (node (ref "U1") (pin "47") (pinfunction "PC4/UARTRX_SFLASH/PWM2_CH5/PWM2_CH1_47") (pintype "passive"))
    )
    (net (code "36") (name "/T1_N") (class "Default")
      (node (ref "RF9") (pin "1") (pintype "passive"))
      (node (ref "U1") (pin "46") (pinfunction "PC3/UARTTX_SFLASH/PWM2_CH4/PWM2_CH0_46") (pintype "passive"))
    )
    (net (code "37") (name "/T2_H") (class "Default")
      (node (ref "RF4") (pin "1") (pintype "passive"))
      (node (ref "U1") (pin "44") (pinfunction "PC1/PWM2_CH2/UART5_RTS_44") (pintype "passive"))
    )
    (net (code "38") (name "/T2_N") (class "Default")
      (node (ref "RF11") (pin "1") (pintype "passive"))
      (node (ref "U1") (pin "45") (pinfunction "PC2/PWM2_CH3/UART6_RTS_45") (pintype "passive"))
    )
    (net (code "39") (name "/TX1") (class "Default")
      (node (ref "CM7") (pin "2") (pintype "passive"))
      (node (ref "RM5") (pin "1") (pintype "passive"))
      (node (ref "U1") (pin "40") (pinfunction "PB13/SPI2_MISO/PWM2_CH4/UART5_TX_40") (pintype "passive"))
    )
    (net (code "40") (name "/TX2") (class "Default")
      (node (ref "CM13") (pin "2") (pintype "passive"))
      (node (ref "RM9") (pin "1") (pintype "passive"))
      (node (ref "U1") (pin "14") (pinfunction "PA7/ADC_IN0/UART1_TX/UART5_TX_14") (pintype "passive"))
    )
    (net (code "41") (name "/TXD1") (class "Default")
      (node (ref "J6") (pin "1") (pinfunction "1_1") (pintype "passive"))
      (node (ref "RM4") (pin "2") (pintype "passive"))
    )
    (net (code "42") (name "/TXD2") (class "Default")
      (node (ref "J8") (pin "1") (pinfunction "1_1") (pintype "passive"))
      (node (ref "RM8") (pin "2") (pintype "passive"))
    )
    (net (code "43") (name "/UART1_CTS") (class "Default")
      (node (ref "RM14") (pin "2") (pintype "passive"))
      (node (ref "U1") (pin "62") (pinfunction "PD0/UART1_CTS/PWM_FAULT2_62") (pintype "passive"))
    )
    (net (code "44") (name "/UART1_RTS") (class "Default")
      (node (ref "RM15") (pin "2") (pintype "passive"))
      (node (ref "U1") (pin "31") (pinfunction "PB7/UART1_RTS/PWM_FAULT1_31") (pintype "passive"))
    )
    (net (code "45") (name "/VIinj1S-") (class "Default")
      (node (ref "CF3") (pin "2") (pinfunction "2_2") (pintype "passive"))
      (node (ref "QF5") (pin "3") (pinfunction "S_3") (pintype "passive"))
      (node (ref "QF7") (pin "2") (pinfunction "D_2") (pintype "passive"))
      (node (ref "RF10") (pin "1") (pintype "passive"))
      (node (ref "UF3") (pin "6") (pinfunction "VS_6") (pintype "passive"))
      (node (ref "UF5") (pin "1") (pinfunction "-IN_1") (pintype "passive"))
    )
    (net (code "46") (name "/VIinj2S-") (class "Default")
      (node (ref "CF4") (pin "2") (pinfunction "2_2") (pintype "passive"))
      (node (ref "QF6") (pin "3") (pinfunction "S_3") (pintype "passive"))
      (node (ref "QF8") (pin "2") (pinfunction "D_2") (pintype "passive"))
      (node (ref "RF12") (pin "1") (pintype "passive"))
      (node (ref "UF4") (pin "6") (pinfunction "VS_6") (pintype "passive"))
      (node (ref "UF6") (pin "1") (pinfunction "-IN_1") (pintype "passive"))
    )
    (net (code "47") (name "/XTAL") (class "Default")
      (node (ref "CM4") (pin "1") (pintype "passive"))
      (node (ref "CR1") (pin "3") (pinfunction "3_3") (pintype "passive"))
      (node (ref "U1") (pin "8") (pinfunction "OSC_IN_8") (pintype "passive"))
    )
    (net (code "48") (name "DVDD") (class "Default")
      (node (ref "CM15") (pin "2") (pintype "passive"))
      (node (ref "CM5") (pin "2") (pintype "passive"))
      (node (ref "CM6") (pin "1") (pintype "passive"))
      (node (ref "LM1") (pin "2") (pintype "passive"))
      (node (ref "U1") (pin "35") (pinfunction "DVDD50_1_35") (pintype "passive"))
      (node (ref "U1") (pin "59") (pinfunction "DVDD50_2_59") (pintype "passive"))
    )
    (net (code "49") (name "GND") (class "Default")
      (node (ref "CC1") (pin "2") (pintype "passive"))
      (node (ref "CC2") (pin "1") (pintype "passive"))
      (node (ref "CC3") (pin "2") (pintype "passive"))
      (node (ref "CF5") (pin "2") (pintype "passive"))
      (node (ref "CF6") (pin "2") (pintype "passive"))
      (node (ref "CF7") (pin "2") (pintype "passive"))
      (node (ref "CF8") (pin "2") (pintype "passive"))
      (node (ref "CM1") (pin "2") (pintype "passive"))
      (node (ref "CM10") (pin "2") (pintype "passive"))
      (node (ref "CM11") (pin "2") (pintype "passive"))
      (node (ref "CM12") (pin "1") (pintype "passive"))
      (node (ref "CM13") (pin "1") (pintype "passive"))
      (node (ref "CM14") (pin "1") (pintype "passive"))
      (node (ref "CM15") (pin "1") (pintype "passive"))
      (node (ref "CM2") (pin "1") (pintype "passive"))
      (node (ref "CM3") (pin "1") (pintype "passive"))
      (node (ref "CM4") (pin "2") (pintype "passive"))
      (node (ref "CM5") (pin "1") (pintype "passive"))
      (node (ref "CM6") (pin "2") (pintype "passive"))
      (node (ref "CM7") (pin "1") (pintype "passive"))
      (node (ref "CM8") (pin "1") (pintype "passive"))
      (node (ref "CM9") (pin "2") (pintype "passive"))
      (node (ref "CR1") (pin "2") (pinfunction "2_2") (pintype "passive"))
      (node (ref "CR1") (pin "4") (pinfunction "4_4") (pintype "passive"))
      (node (ref "CS1") (pin "2") (pintype "passive"))
      (node (ref "CS3") (pin "2") (pintype "passive"))
      (node (ref "CS4") (pin "2") (pintype "passive"))
      (node (ref "CS5") (pin "2") (pintype "passive"))
      (node (ref "CS6") (pin "2") (pintype "passive"))
      (node (ref "CS7") (pin "2") (pintype "passive"))
      (node (ref "CS8") (pin "2") (pintype "passive"))
      (node (ref "J7") (pin "1") (pinfunction "1_1") (pintype "passive"))
      (node (ref "LP1") (pin "2") (pintype "passive"))
      (node (ref "P1") (pin "1") (pinfunction "1_1") (pintype "passive"))
      (node (ref "RC1") (pin "2") (pintype "passive"))
      (node (ref "RM12") (pin "1") (pintype "passive"))
      (node (ref "RM14") (pin "1") (pintype "passive"))
      (node (ref "RM15") (pin "1") (pintype "passive"))
      (node (ref "RM16") (pin "1") (pintype "passive"))
      (node (ref "RS11") (pin "1") (pintype "passive"))
      (node (ref "RS8") (pin "1") (pintype "passive"))
      (node (ref "U1") (pin "12") (pinfunction "AVSS50_IO_12") (pintype "passive"))
      (node (ref "U1") (pin "34") (pinfunction "DVSS50_1_34") (pintype "passive"))
      (node (ref "U1") (pin "58") (pinfunction "DVSS50_2_58") (pintype "passive"))
      (node (ref "U1") (pin "9") (pinfunction "AVSS50_9") (pintype "passive"))
      (node (ref "UC1") (pin "2") (pinfunction "GND_2") (pintype "passive"))
      (node (ref "UF5") (pin "2") (pinfunction "Vss_2") (pintype "passive"))
      (node (ref "UF5") (pin "3") (pinfunction "Vref2_3") (pintype "passive"))
      (node (ref "UF6") (pin "2") (pinfunction "Vss_2") (pintype "passive"))
      (node (ref "UF6") (pin "3") (pinfunction "Vref2_3") (pintype "passive"))
      (node (ref "ZM1") (pin "A") (pinfunction "1_A") (pintype "passive"))
      (node (ref "ZM1") (pin "NC") (pinfunction "2_NC") (pintype "passive"))
      (node (ref "ZM2") (pin "A") (pinfunction "1_A") (pintype "passive"))
      (node (ref "ZM2") (pin "NC") (pinfunction "2_NC") (pintype "passive"))
    )
    (net (code "50") (name "Net-(CC3-Pad1)") (class "Default")
      (node (ref "CC3") (pin "1") (pintype "passive"))
      (node (ref "RC2") (pin "1") (pintype "passive"))
      (node (ref "RC3") (pin "1") (pintype "passive"))
    )
    (net (code "51") (name "Net-(QF1-Pad1)") (class "Default")
      (node (ref "QF1") (pin "1") (pinfunction "1_1") (pintype "passive"))
      (node (ref "RF1") (pin "2") (pintype "passive"))
    )
    (net (code "52") (name "Net-(QF2-Pad1)") (class "Default")
      (node (ref "QF2") (pin "1") (pinfunction "1_1") (pintype "passive"))
      (node (ref "RF2") (pin "2") (pintype "passive"))
    )
    (net (code "53") (name "Net-(QF3-Pad1)") (class "Default")
      (node (ref "QF3") (pin "1") (pinfunction "1_1") (pintype "passive"))
      (node (ref "RF5") (pin "2") (pintype "passive"))
    )
    (net (code "54") (name "Net-(QF4-Pad1)") (class "Default")
      (node (ref "QF4") (pin "1") (pinfunction "1_1") (pintype "passive"))
      (node (ref "RF6") (pin "2") (pintype "passive"))
    )
    (net (code "55") (name "Net-(QF5-Pad1)") (class "Default")
      (node (ref "QF5") (pin "1") (pinfunction "1_1") (pintype "passive"))
      (node (ref "RF7") (pin "2") (pintype "passive"))
    )
    (net (code "56") (name "Net-(QF6-Pad1)") (class "Default")
      (node (ref "QF6") (pin "1") (pinfunction "1_1") (pintype "passive"))
      (node (ref "RF8") (pin "2") (pintype "passive"))
    )
    (net (code "57") (name "Net-(QF7-Pad1)") (class "Default")
      (node (ref "QF7") (pin "1") (pinfunction "1_1") (pintype "passive"))
      (node (ref "RF13") (pin "2") (pintype "passive"))
    )
    (net (code "58") (name "Net-(QF8-Pad1)") (class "Default")
      (node (ref "QF8") (pin "1") (pinfunction "1_1") (pintype "passive"))
      (node (ref "RF14") (pin "2") (pintype "passive"))
    )
    (net (code "59") (name "Net-(RM4-Pad1)") (class "Default")
      (node (ref "RM4") (pin "1") (pintype "passive"))
      (node (ref "RM5") (pin "2") (pintype "passive"))
      (node (ref "ZM1") (pin "K") (pinfunction "2_K") (pintype "passive"))
    )
    (net (code "60") (name "Net-(RM8-Pad1)") (class "Default")
      (node (ref "RM8") (pin "1") (pintype "passive"))
      (node (ref "RM9") (pin "2") (pintype "passive"))
      (node (ref "ZM2") (pin "K") (pinfunction "2_K") (pintype "passive"))
    )
    (net (code "61") (name "Net-(RS1-Pad2)") (class "Default")
      (node (ref "RS1") (pin "2") (pintype "passive"))
      (node (ref "RS2") (pin "1") (pintype "passive"))
      (node (ref "RS5") (pin "2") (pintype "passive"))
    )
    (net (code "62") (name "Net-(UC1-CANH)") (class "Default")
      (node (ref "LC1") (pin "1") (pinfunction "1_1") (pintype "passive"))
      (node (ref "UC1") (pin "7") (pinfunction "CANH_7") (pintype "passive"))
    )
    (net (code "63") (name "Net-(UC1-CANL)") (class "Default")
      (node (ref "LC1") (pin "2") (pinfunction "2_2") (pintype "passive"))
      (node (ref "UC1") (pin "6") (pinfunction "CANL_6") (pintype "passive"))
    )
    (net (code "64") (name "Net-(UC1-STB)") (class "Default")
      (node (ref "RC1") (pin "1") (pintype "passive"))
      (node (ref "UC1") (pin "8") (pinfunction "STB_8") (pintype "passive"))
    )
    (net (code "65") (name "Net-(UF1-HIN)") (class "Default")
      (node (ref "RF3") (pin "2") (pintype "passive"))
      (node (ref "UF1") (pin "2") (pinfunction "HIN_2") (pintype "passive"))
      (node (ref "UF1") (pin "3") (pinfunction "~{LIN}_3") (pintype "passive"))
    )
    (net (code "66") (name "Net-(UF1-HO)") (class "Default")
      (node (ref "RF1") (pin "1") (pintype "passive"))
      (node (ref "UF1") (pin "7") (pinfunction "HO_7") (pintype "passive"))
    )
    (net (code "67") (name "Net-(UF1-LO)") (class "Default")
      (node (ref "RF5") (pin "1") (pintype "passive"))
      (node (ref "UF1") (pin "5") (pinfunction "LO_5") (pintype "passive"))
    )
    (net (code "68") (name "Net-(UF1-VB)") (class "Default")
      (node (ref "CF1") (pin "1") (pinfunction "1_1") (pintype "passive"))
      (node (ref "DF1") (pin "2") (pinfunction "2_2") (pintype "passive"))
      (node (ref "UF1") (pin "8") (pinfunction "VB_8") (pintype "passive"))
    )
    (net (code "69") (name "Net-(UF2-HIN)") (class "Default")
      (node (ref "RF4") (pin "2") (pintype "passive"))
      (node (ref "UF2") (pin "2") (pinfunction "HIN_2") (pintype "passive"))
      (node (ref "UF2") (pin "3") (pinfunction "~{LIN}_3") (pintype "passive"))
    )
    (net (code "70") (name "Net-(UF2-HO)") (class "Default")
      (node (ref "RF2") (pin "1") (pintype "passive"))
      (node (ref "UF2") (pin "7") (pinfunction "HO_7") (pintype "passive"))
    )
    (net (code "71") (name "Net-(UF2-LO)") (class "Default")
      (node (ref "RF6") (pin "1") (pintype "passive"))
      (node (ref "UF2") (pin "5") (pinfunction "LO_5") (pintype "passive"))
    )
    (net (code "72") (name "Net-(UF2-VB)") (class "Default")
      (node (ref "CF2") (pin "1") (pinfunction "1_1") (pintype "passive"))
      (node (ref "DF2") (pin "2") (pinfunction "2_2") (pintype "passive"))
      (node (ref "UF2") (pin "8") (pinfunction "VB_8") (pintype "passive"))
    )
    (net (code "73") (name "Net-(UF3-HIN)") (class "Default")
      (node (ref "RF9") (pin "2") (pintype "passive"))
      (node (ref "UF3") (pin "2") (pinfunction "HIN_2") (pintype "passive"))
      (node (ref "UF3") (pin "3") (pinfunction "~{LIN}_3") (pintype "passive"))
    )
    (net (code "74") (name "Net-(UF3-HO)") (class "Default")
      (node (ref "RF7") (pin "1") (pintype "passive"))
      (node (ref "UF3") (pin "7") (pinfunction "HO_7") (pintype "passive"))
    )
    (net (code "75") (name "Net-(UF3-LO)") (class "Default")
      (node (ref "RF13") (pin "1") (pintype "passive"))
      (node (ref "UF3") (pin "5") (pinfunction "LO_5") (pintype "passive"))
    )
    (net (code "76") (name "Net-(UF3-VB)") (class "Default")
      (node (ref "CF3") (pin "1") (pinfunction "1_1") (pintype "passive"))
      (node (ref "DF5") (pin "2") (pinfunction "2_2") (pintype "passive"))
      (node (ref "UF3") (pin "8") (pinfunction "VB_8") (pintype "passive"))
    )
    (net (code "77") (name "Net-(UF4-HIN)") (class "Default")
      (node (ref "RF11") (pin "2") (pintype "passive"))
      (node (ref "UF4") (pin "2") (pinfunction "HIN_2") (pintype "passive"))
      (node (ref "UF4") (pin "3") (pinfunction "~{LIN}_3") (pintype "passive"))
    )
    (net (code "78") (name "Net-(UF4-HO)") (class "Default")
      (node (ref "RF8") (pin "1") (pintype "passive"))
      (node (ref "UF4") (pin "7") (pinfunction "HO_7") (pintype "passive"))
    )
    (net (code "79") (name "Net-(UF4-LO)") (class "Default")
      (node (ref "RF14") (pin "1") (pintype "passive"))
      (node (ref "UF4") (pin "5") (pinfunction "LO_5") (pintype "passive"))
    )
    (net (code "80") (name "Net-(UF4-VB)") (class "Default")
      (node (ref "CF4") (pin "1") (pinfunction "1_1") (pintype "passive"))
      (node (ref "DF6") (pin "2") (pinfunction "2_2") (pintype "passive"))
      (node (ref "UF4") (pin "8") (pinfunction "VB_8") (pintype "passive"))
    )
    (net (code "81") (name "Net-(UP2-IN)") (class "Default")
      (node (ref "CP6") (pin "1") (pintype "passive"))
      (node (ref "DP1") (pin "2") (pinfunction "2_2") (pintype "passive"))
      (node (ref "UP2") (pin "3") (pinfunction "IN_3") (pintype "passive"))
    )
    (net (code "82") (name "Net-(UP4-FREQ)") (class "Default")
      (node (ref "RP3") (pin "2") (pintype "passive"))
      (node (ref "UP4") (pin "5") (pinfunction "FREQ_5") (pintype "passive"))
    )
    (net (code "83") (name "Net-(UP4-SWO)") (class "Default")
      (node (ref "DP4") (pin "K") (pintype "passive"))
      (node (ref "LP2") (pin "1") (pinfunction "1_1") (pintype "passive"))
      (node (ref "UP4") (pin "11") (pinfunction "SWO_11") (pintype "passive"))
    )
    (net (code "84") (name "PGND") (class "Default")
      (node (ref "C1") (pin "2") (pintype "passive"))
      (node (ref "C2") (pin "2") (pintype "passive"))
      (node (ref "C3") (pin "2") (pintype "passive"))
      (node (ref "CP1") (pin "2") (pintype "passive"))
      (node (ref "CP10") (pin "2") (pintype "passive"))
      (node (ref "CP2") (pin "2") (pintype "passive"))
      (node (ref "CP3") (pin "2") (pintype "passive"))
      (node (ref "CP4") (pin "2") (pintype "passive"))
      (node (ref "CP5") (pin "2") (pintype "passive"))
      (node (ref "CP6") (pin "2") (pintype "passive"))
      (node (ref "CP7") (pin "2") (pintype "passive"))
      (node (ref "CP8") (pin "2") (pinfunction "2_2") (pintype "passive"))
      (node (ref "CP9") (pin "2") (pintype "passive"))
      (node (ref "CS2") (pin "2") (pintype "passive"))
      (node (ref "DC1") (pin "3") (pinfunction "G_3") (pintype "passive"))
      (node (ref "DF3") (pin "3") (pinfunction "G_3") (pintype "passive"))
      (node (ref "DF4") (pin "3") (pinfunction "G_3") (pintype "passive"))
      (node (ref "DP4") (pin "A") (pintype "passive"))
      (node (ref "J2") (pin "2") (pinfunction "2_2") (pintype "passive"))
      (node (ref "J3") (pin "1") (pinfunction "1_1") (pintype "passive"))
      (node (ref "LP1") (pin "1") (pintype "passive"))
      (node (ref "QF3") (pin "3") (pinfunction "S_3") (pintype "passive"))
      (node (ref "QF4") (pin "3") (pinfunction "S_3") (pintype "passive"))
      (node (ref "QF7") (pin "3") (pinfunction "S_3") (pintype "passive"))
      (node (ref "QF8") (pin "3") (pinfunction "S_3") (pintype "passive"))
      (node (ref "RP3") (pin "1") (pintype "passive"))
      (node (ref "RS5") (pin "1") (pintype "passive"))
      (node (ref "UF1") (pin "4") (pinfunction "COM_4") (pintype "passive"))
      (node (ref "UF2") (pin "4") (pinfunction "COM_4") (pintype "passive"))
      (node (ref "UF3") (pin "4") (pinfunction "COM_4") (pintype "passive"))
      (node (ref "UF4") (pin "4") (pinfunction "COM_4") (pintype "passive"))
      (node (ref "UP2") (pin "2") (pinfunction "GND_2") (pintype "passive"))
      (node (ref "UP4") (pin "0") (pinfunction "EP_0") (pintype "passive"))
      (node (ref "UP4") (pin "1") (pinfunction "NC_1") (pintype "passive"))
      (node (ref "UP4") (pin "10") (pinfunction "GND_10") (pintype "passive"))
      (node (ref "UP4") (pin "12") (pinfunction "NC_12") (pintype "passive"))
      (node (ref "UP4") (pin "14") (pinfunction "NC_14") (pintype "passive"))
      (node (ref "UP4") (pin "2") (pinfunction "NC_2") (pintype "passive"))
      (node (ref "UP4") (pin "3") (pinfunction "NC_3") (pintype "passive"))
      (node (ref "UP4") (pin "4") (pinfunction "SYNC_4") (pintype "passive"))
      (node (ref "UP4") (pin "6") (pinfunction "NC_6") (pintype "passive"))
      (node (ref "UP4") (pin "8") (pinfunction "NC_8") (pintype "passive"))
      (node (ref "UP4") (pin "9") (pinfunction "GND_9") (pintype "passive"))
    )
    (net (code "85") (name "VBAT") (class "Default")
      (node (ref "C1") (pin "1") (pintype "passive"))
      (node (ref "C2") (pin "1") (pintype "passive"))
      (node (ref "CS2") (pin "1") (pintype "passive"))
      (node (ref "J3") (pin "2") (pinfunction "2_2") (pintype "passive"))
      (node (ref "QF1") (pin "2") (pinfunction "D_2") (pintype "passive"))
      (node (ref "QF2") (pin "2") (pinfunction "D_2") (pintype "passive"))
      (node (ref "QF5") (pin "2") (pinfunction "D_2") (pintype "passive"))
      (node (ref "QF6") (pin "2") (pinfunction "D_2") (pintype "passive"))
      (node (ref "RS2") (pin "2") (pintype "passive"))
    )
    (net (code "86") (name "VCC") (class "Default")
      (node (ref "C3") (pin "1") (pintype "passive"))
      (node (ref "CC1") (pin "1") (pintype "passive"))
      (node (ref "CC2") (pin "2") (pintype "passive"))
      (node (ref "CF5") (pin "1") (pintype "passive"))
      (node (ref "CF6") (pin "1") (pintype "passive"))
      (node (ref "CM11") (pin "1") (pintype "passive"))
      (node (ref "CM14") (pin "2") (pintype "passive"))
      (node (ref "CP3") (pin "1") (pintype "passive"))
      (node (ref "CP4") (pin "1") (pintype "passive"))
      (node (ref "CP5") (pin "1") (pintype "passive"))
      (node (ref "J7") (pin "2") (pinfunction "2_2") (pintype "passive"))
      (node (ref "LM1") (pin "1") (pintype "passive"))
      (node (ref "LM2") (pin "2") (pintype "passive"))
      (node (ref "LP2") (pin "2") (pinfunction "2_2") (pintype "passive"))
      (node (ref "P1") (pin "4") (pinfunction "4_4") (pintype "passive"))
      (node (ref "RM1") (pin "2") (pintype "passive"))
      (node (ref "RM13") (pin "1") (pintype "passive"))
      (node (ref "RM2") (pin "2") (pintype "passive"))
      (node (ref "RM6") (pin "2") (pintype "passive"))
      (node (ref "RS3") (pin "1") (pintype "passive"))
      (node (ref "RS6") (pin "1") (pintype "passive"))
      (node (ref "UC1") (pin "3") (pinfunction "Vcc_3") (pintype "passive"))
      (node (ref "UC1") (pin "5") (pinfunction "Vio_5") (pintype "passive"))
      (node (ref "UF5") (pin "6") (pinfunction "VCC_6") (pintype "passive"))
      (node (ref "UF5") (pin "7") (pinfunction "Vref1_7") (pintype "passive"))
      (node (ref "UF6") (pin "6") (pinfunction "VCC_6") (pintype "passive"))
      (node (ref "UF6") (pin "7") (pinfunction "Vref1_7") (pintype "passive"))
      (node (ref "UP4") (pin "7") (pinfunction "FB_7") (pintype "passive"))
    )
    (net (code "87") (name "unconnected-(U1-PA0{slash}SPI1_NSS{slash}TRACED3{slash}FLASH_NSS-Pad1)") (class "Default")
      (node (ref "U1") (pin "1") (pinfunction "PA0/SPI1_NSS/TRACED3/FLASH_NSS_1") (pintype "passive"))
    )
    (net (code "88") (name "unconnected-(U1-PA1{slash}SPI1_SCK{slash}TRACECLK{slash}FLASH_SCK-Pad2)") (class "Default")
      (node (ref "U1") (pin "2") (pinfunction "PA1/SPI1_SCK/TRACECLK/FLASH_SCK_2") (pintype "passive"))
    )
    (net (code "89") (name "unconnected-(U1-PA2{slash}SPI1_MISO{slash}TRACED0{slash}FLASH_DQ1-Pad3)") (class "Default")
      (node (ref "U1") (pin "3") (pinfunction "PA2/SPI1_MISO/TRACED0/FLASH_DQ1_3") (pintype "passive"))
    )
    (net (code "90") (name "unconnected-(U1-PA3{slash}SPI1_MOSI{slash}TRACED1{slash}FLASH_DQ0-Pad4)") (class "Default")
      (node (ref "U1") (pin "4") (pinfunction "PA3/SPI1_MOSI/TRACED1/FLASH_DQ0_4") (pintype "passive"))
    )
    (net (code "91") (name "unconnected-(U1-PA4{slash}UART4_TX{slash}CAN1_RX{slash}FLASH_DQ3-Pad5)") (class "Default")
      (node (ref "U1") (pin "5") (pinfunction "PA4/UART4_TX/CAN1_RX/FLASH_DQ3_5") (pintype "passive"))
    )
    (net (code "92") (name "unconnected-(U1-PA5{slash}UART4_RX{slash}CAN1_TX{slash}FLASH_DQ2-Pad6)") (class "Default")
      (node (ref "U1") (pin "6") (pinfunction "PA5/UART4_RX/CAN1_TX/FLASH_DQ2_6") (pintype "passive"))
    )
    (net (code "93") (name "unconnected-(U1-PA6{slash}ADC_IN10{slash}UART1_CTS{slash}UART4_TX-Pad13)") (class "Default")
      (node (ref "U1") (pin "13") (pinfunction "PA6/ADC_IN10/UART1_CTS/UART4_TX_13") (pintype "passive"))
    )
    (net (code "94") (name "unconnected-(U1-PA9{slash}ADC_IN2{slash}SPI2_NSS{slash}HWLIN_TX-Pad16)") (class "Default")
      (node (ref "U1") (pin "16") (pinfunction "PA9/ADC_IN2/SPI2_NSS/HWLIN_TX_16") (pintype "passive"))
    )
    (net (code "95") (name "unconnected-(U1-PB1{slash}ADC_IN11{slash}UART2_RX-Pad24)") (class "Default")
      (node (ref "U1") (pin "24") (pinfunction "PB1/ADC_IN11/UART2_RX_24") (pintype "passive"))
    )
    (net (code "96") (name "unconnected-(U1-PB2{slash}NMI_B{slash}UART3_TX{slash}CAN1_STDBY-Pad25)") (class "Default")
      (node (ref "U1") (pin "25") (pinfunction "PB2/NMI_B/UART3_TX/CAN1_STDBY_25") (pintype "passive"))
    )
    (net (code "97") (name "unconnected-(U1-PB3{slash}PWDT_IN1{slash}UART3_RX-Pad27)") (class "Default")
      (node (ref "U1") (pin "27") (pinfunction "PB3/PWDT_IN1/UART3_RX_27") (pintype "passive"))
    )
    (net (code "98") (name "unconnected-(U1-PB4{slash}PWDT_IN2{slash}TRACED2-Pad28)") (class "Default")
      (node (ref "U1") (pin "28") (pinfunction "PB4/PWDT_IN2/TRACED2_28") (pintype "passive"))
    )
    (net (code "99") (name "unconnected-(U1-PB5{slash}UART1_TX{slash}PWDT_IN1-Pad29)") (class "Default")
      (node (ref "U1") (pin "29") (pinfunction "PB5/UART1_TX/PWDT_IN1_29") (pintype "passive"))
    )
    (net (code "100") (name "unconnected-(U1-PB6{slash}UART1_RX{slash}PWDT_IN2{slash}PWM3_CH0-Pad30)") (class "Default")
      (node (ref "U1") (pin "30") (pinfunction "PB6/UART1_RX/PWDT_IN2/PWM3_CH0_30") (pintype "passive"))
    )
    (net (code "101") (name "unconnected-(U1-PB8{slash}PWDT_IN0{slash}I2C2_SDA-Pad32)") (class "Default")
      (node (ref "U1") (pin "32") (pinfunction "PB8/PWDT_IN0/I2C2_SDA_32") (pintype "passive"))
    )
    (net (code "102") (name "unconnected-(U1-PB9{slash}PWM0_CH0{slash}PWM2_CH0{slash}CAN1_RX-Pad33)") (class "Default")
      (node (ref "U1") (pin "33") (pinfunction "PB9/PWM0_CH0/PWM2_CH0/CAN1_RX_33") (pintype "passive"))
    )
    (net (code "103") (name "unconnected-(U1-PB10{slash}PWM0_CH1{slash}PWM2_CH1{slash}CAN1_TX-Pad37)") (class "Default")
      (node (ref "U1") (pin "37") (pinfunction "PB10/PWM0_CH1/PWM2_CH1/CAN1_TX_37") (pintype "passive"))
    )
    (net (code "104") (name "unconnected-(U1-PB11{slash}SPI2_NSS{slash}PWM2_CH2-Pad38)") (class "Default")
      (node (ref "U1") (pin "38") (pinfunction "PB11/SPI2_NSS/PWM2_CH2_38") (pintype "passive"))
    )
    (net (code "105") (name "unconnected-(U1-PB12{slash}SPI2_SCK{slash}PWM2_CH3-Pad39)") (class "Default")
      (node (ref "U1") (pin "39") (pinfunction "PB12/SPI2_SCK/PWM2_CH3_39") (pintype "passive"))
    )
    (net (code "106") (name "unconnected-(U1-PB15{slash}PWM2_CH0{slash}PWM0_EXT-Pad42)") (class "Default")
      (node (ref "U1") (pin "42") (pinfunction "PB15/PWM2_CH0/PWM0_EXT_42") (pintype "passive"))
    )
    (net (code "107") (name "unconnected-(U1-PC0{slash}PWM2_CH1{slash}PWM1_EXT-Pad43)") (class "Default")
      (node (ref "U1") (pin "43") (pinfunction "PC0/PWM2_CH1/PWM1_EXT_43") (pintype "passive"))
    )
    (net (code "108") (name "unconnected-(U1-PC5{slash}I2C2_SCL{slash}UART1_CTS-Pad48)") (class "Default")
      (node (ref "U1") (pin "48") (pinfunction "PC5/I2C2_SCL/UART1_CTS_48") (pintype "passive"))
    )
    (net (code "109") (name "unconnected-(U1-PC6{slash}I2C2_SDA{slash}UART1_CTS-Pad49)") (class "Default")
      (node (ref "U1") (pin "49") (pinfunction "PC6/I2C2_SDA/UART1_CTS_49") (pintype "passive"))
    )
    (net (code "110") (name "unconnected-(U1-PC8{slash}JTDO_TRACESWO{slash}UART2_RTS-Pad51)") (class "Default")
      (node (ref "U1") (pin "51") (pinfunction "PC8/JTDO_TRACESWO/UART2_RTS_51") (pintype "passive"))
    )
    (net (code "111") (name "unconnected-(U1-PC12{slash}I2C1_SCL{slash}UART5_TX-Pad56)") (class "Default")
      (node (ref "U1") (pin "56") (pinfunction "PC12/I2C1_SCL/UART5_TX_56") (pintype "passive"))
    )
    (net (code "112") (name "unconnected-(U1-PC13{slash}I2C1_SDA{slash}UART5_RX-Pad57)") (class "Default")
      (node (ref "U1") (pin "57") (pinfunction "PC13/I2C1_SDA/UART5_RX_57") (pintype "passive"))
    )
    (net (code "113") (name "unconnected-(U1-PC14{slash}CAN1_RX{slash}UART4_RX{slash}PWDT_IN3-Pad60)") (class "Default")
      (node (ref "U1") (pin "60") (pinfunction "PC14/CAN1_RX/UART4_RX/PWDT_IN3_60") (pintype "passive"))
    )
    (net (code "114") (name "unconnected-(U1-PC15{slash}CAN1_TX{slash}UART4_TX-Pad61)") (class "Default")
      (node (ref "U1") (pin "61") (pinfunction "PC15/CAN1_TX/UART4_TX_61") (pintype "passive"))
    )
    (net (code "115") (name "unconnected-(U1-PD1{slash}UART2_TX{slash}PWM0_CH0{slash}I2C2_SCL-Pad63)") (class "Default")
      (node (ref "U1") (pin "63") (pinfunction "PD1/UART2_TX/PWM0_CH0/I2C2_SCL_63") (pintype "passive"))
    )
    (net (code "116") (name "unconnected-(U1-PD2{slash}UART2_RX{slash}PWM0_CH1{slash}I2C2_SDA-Pad64)") (class "Default")
      (node (ref "U1") (pin "64") (pinfunction "PD2/UART2_RX/PWM0_CH1/I2C2_SDA_64") (pintype "passive"))
    )
    (net (code "117") (name "unconnected-(U1-VPP-Pad36)") (class "Default")
      (node (ref "U1") (pin "36") (pinfunction "VPP_36") (pintype "passive"))
    )
    (net (code "118") (name "unconnected-(UF5-NC-Pad4)") (class "Default")
      (node (ref "UF5") (pin "4") (pinfunction "NC_4") (pintype "power_in+no_connect"))
    )
    (net (code "119") (name "unconnected-(UF6-NC-Pad4)") (class "Default")
      (node (ref "UF6") (pin "4") (pinfunction "NC_4") (pintype "power_in+no_connect"))
    )
  )
)
